# io-board-c-5.net
KiCad netlist of a schematic drawn in EAGLE
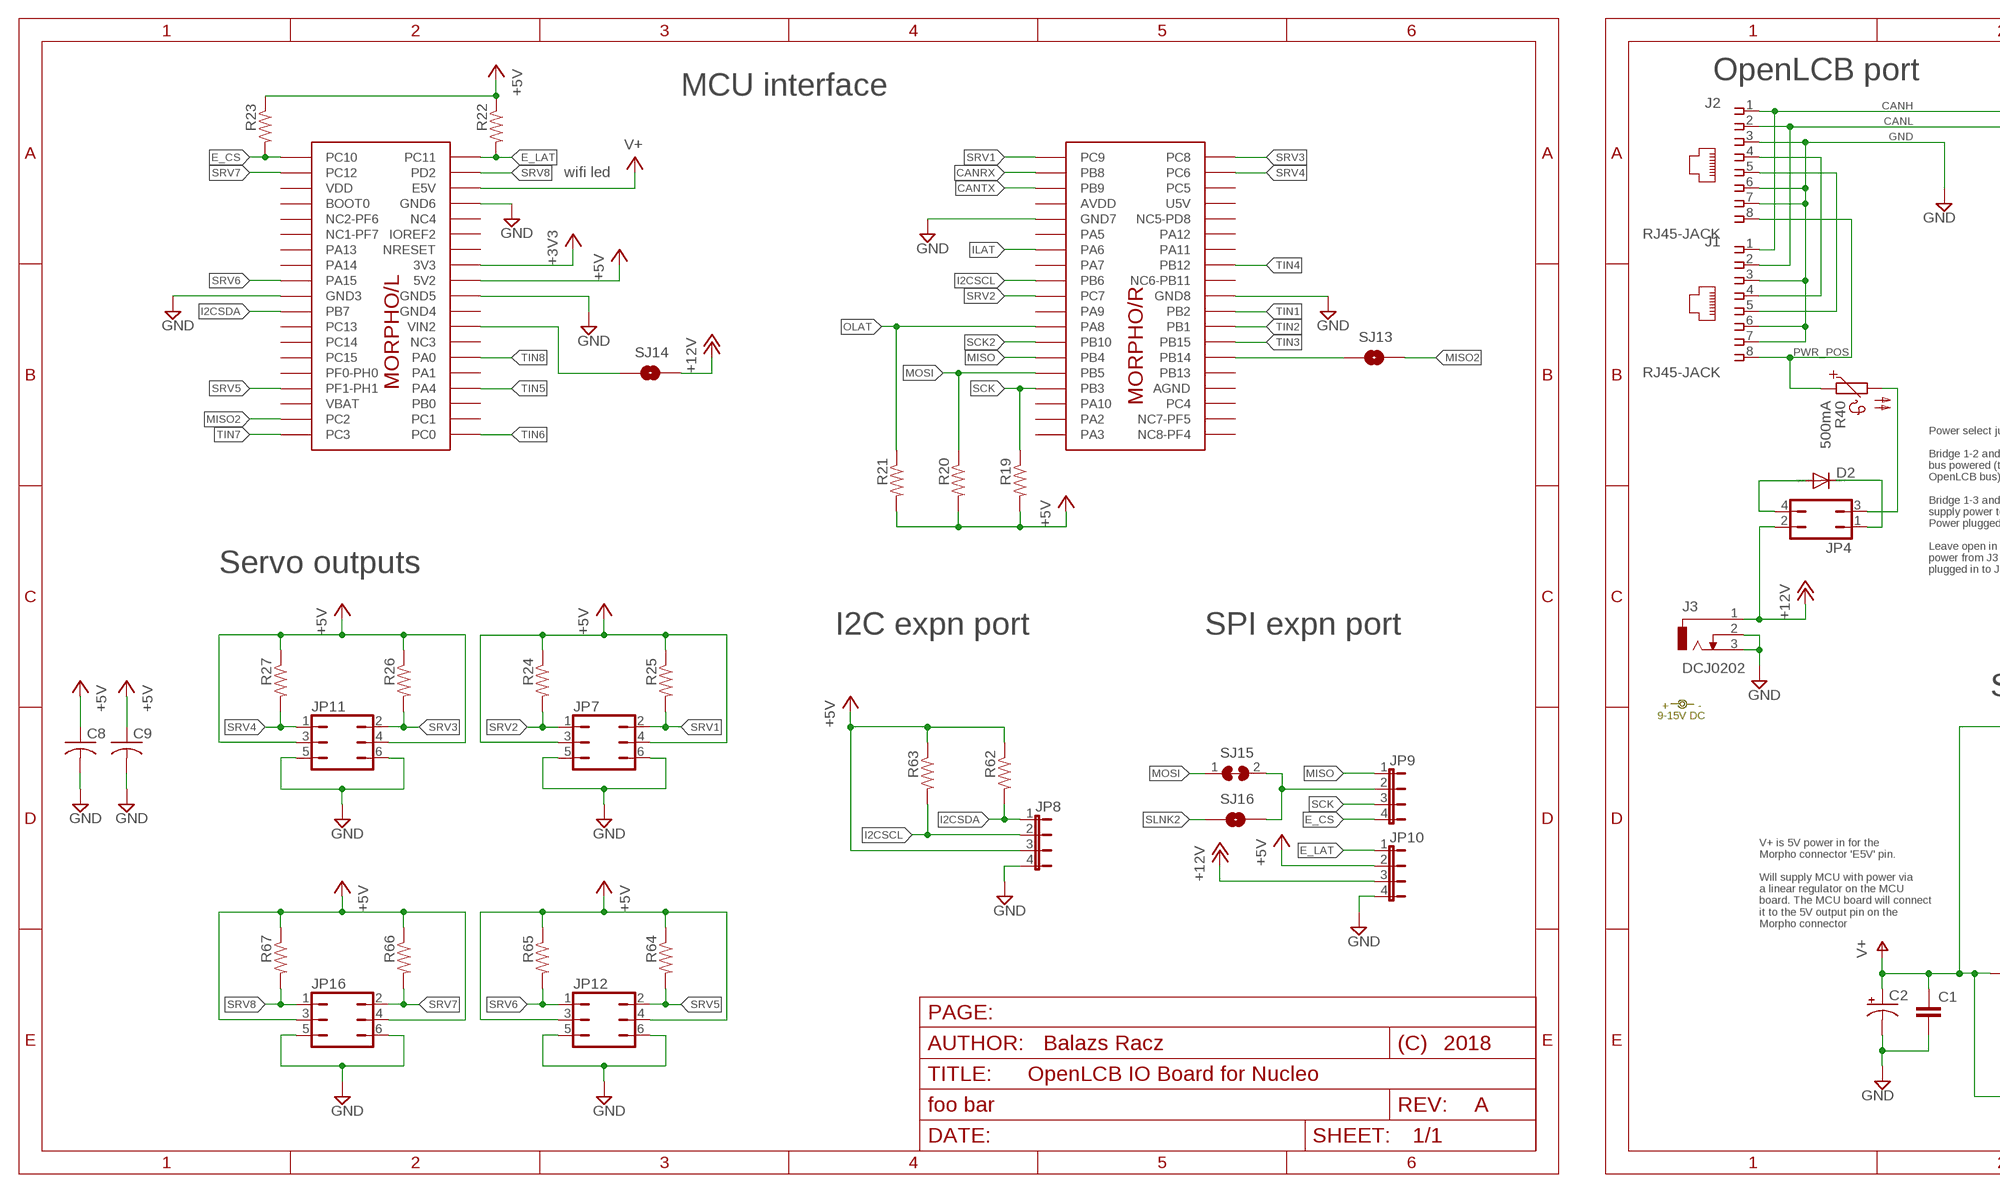
[diagram p0: schematic, sheet 1, part 1 of 3]
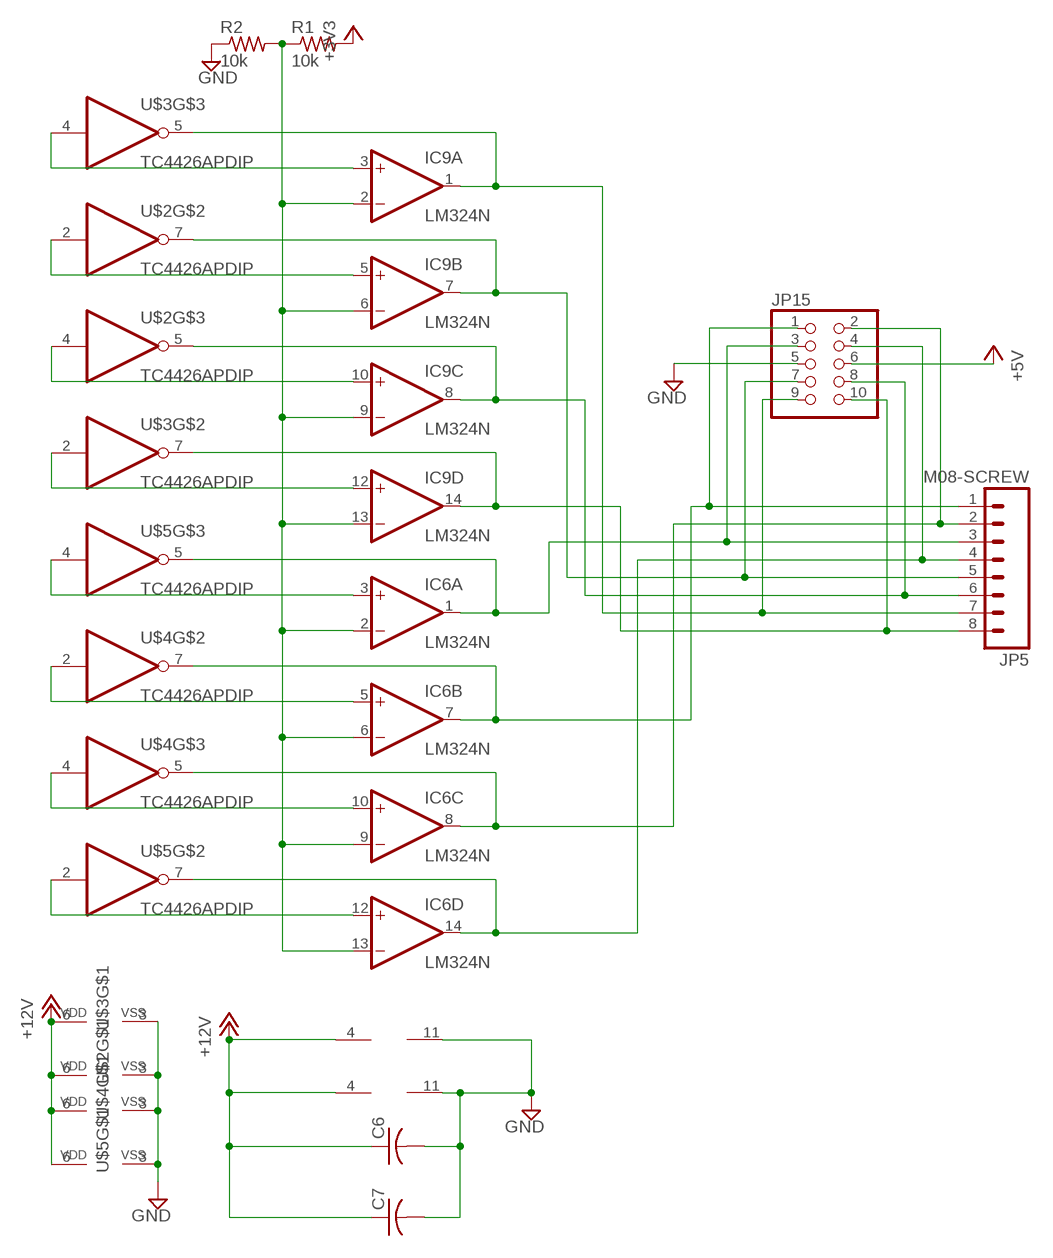
[diagram p1: schematic, sheet 1, part 2 of 3]
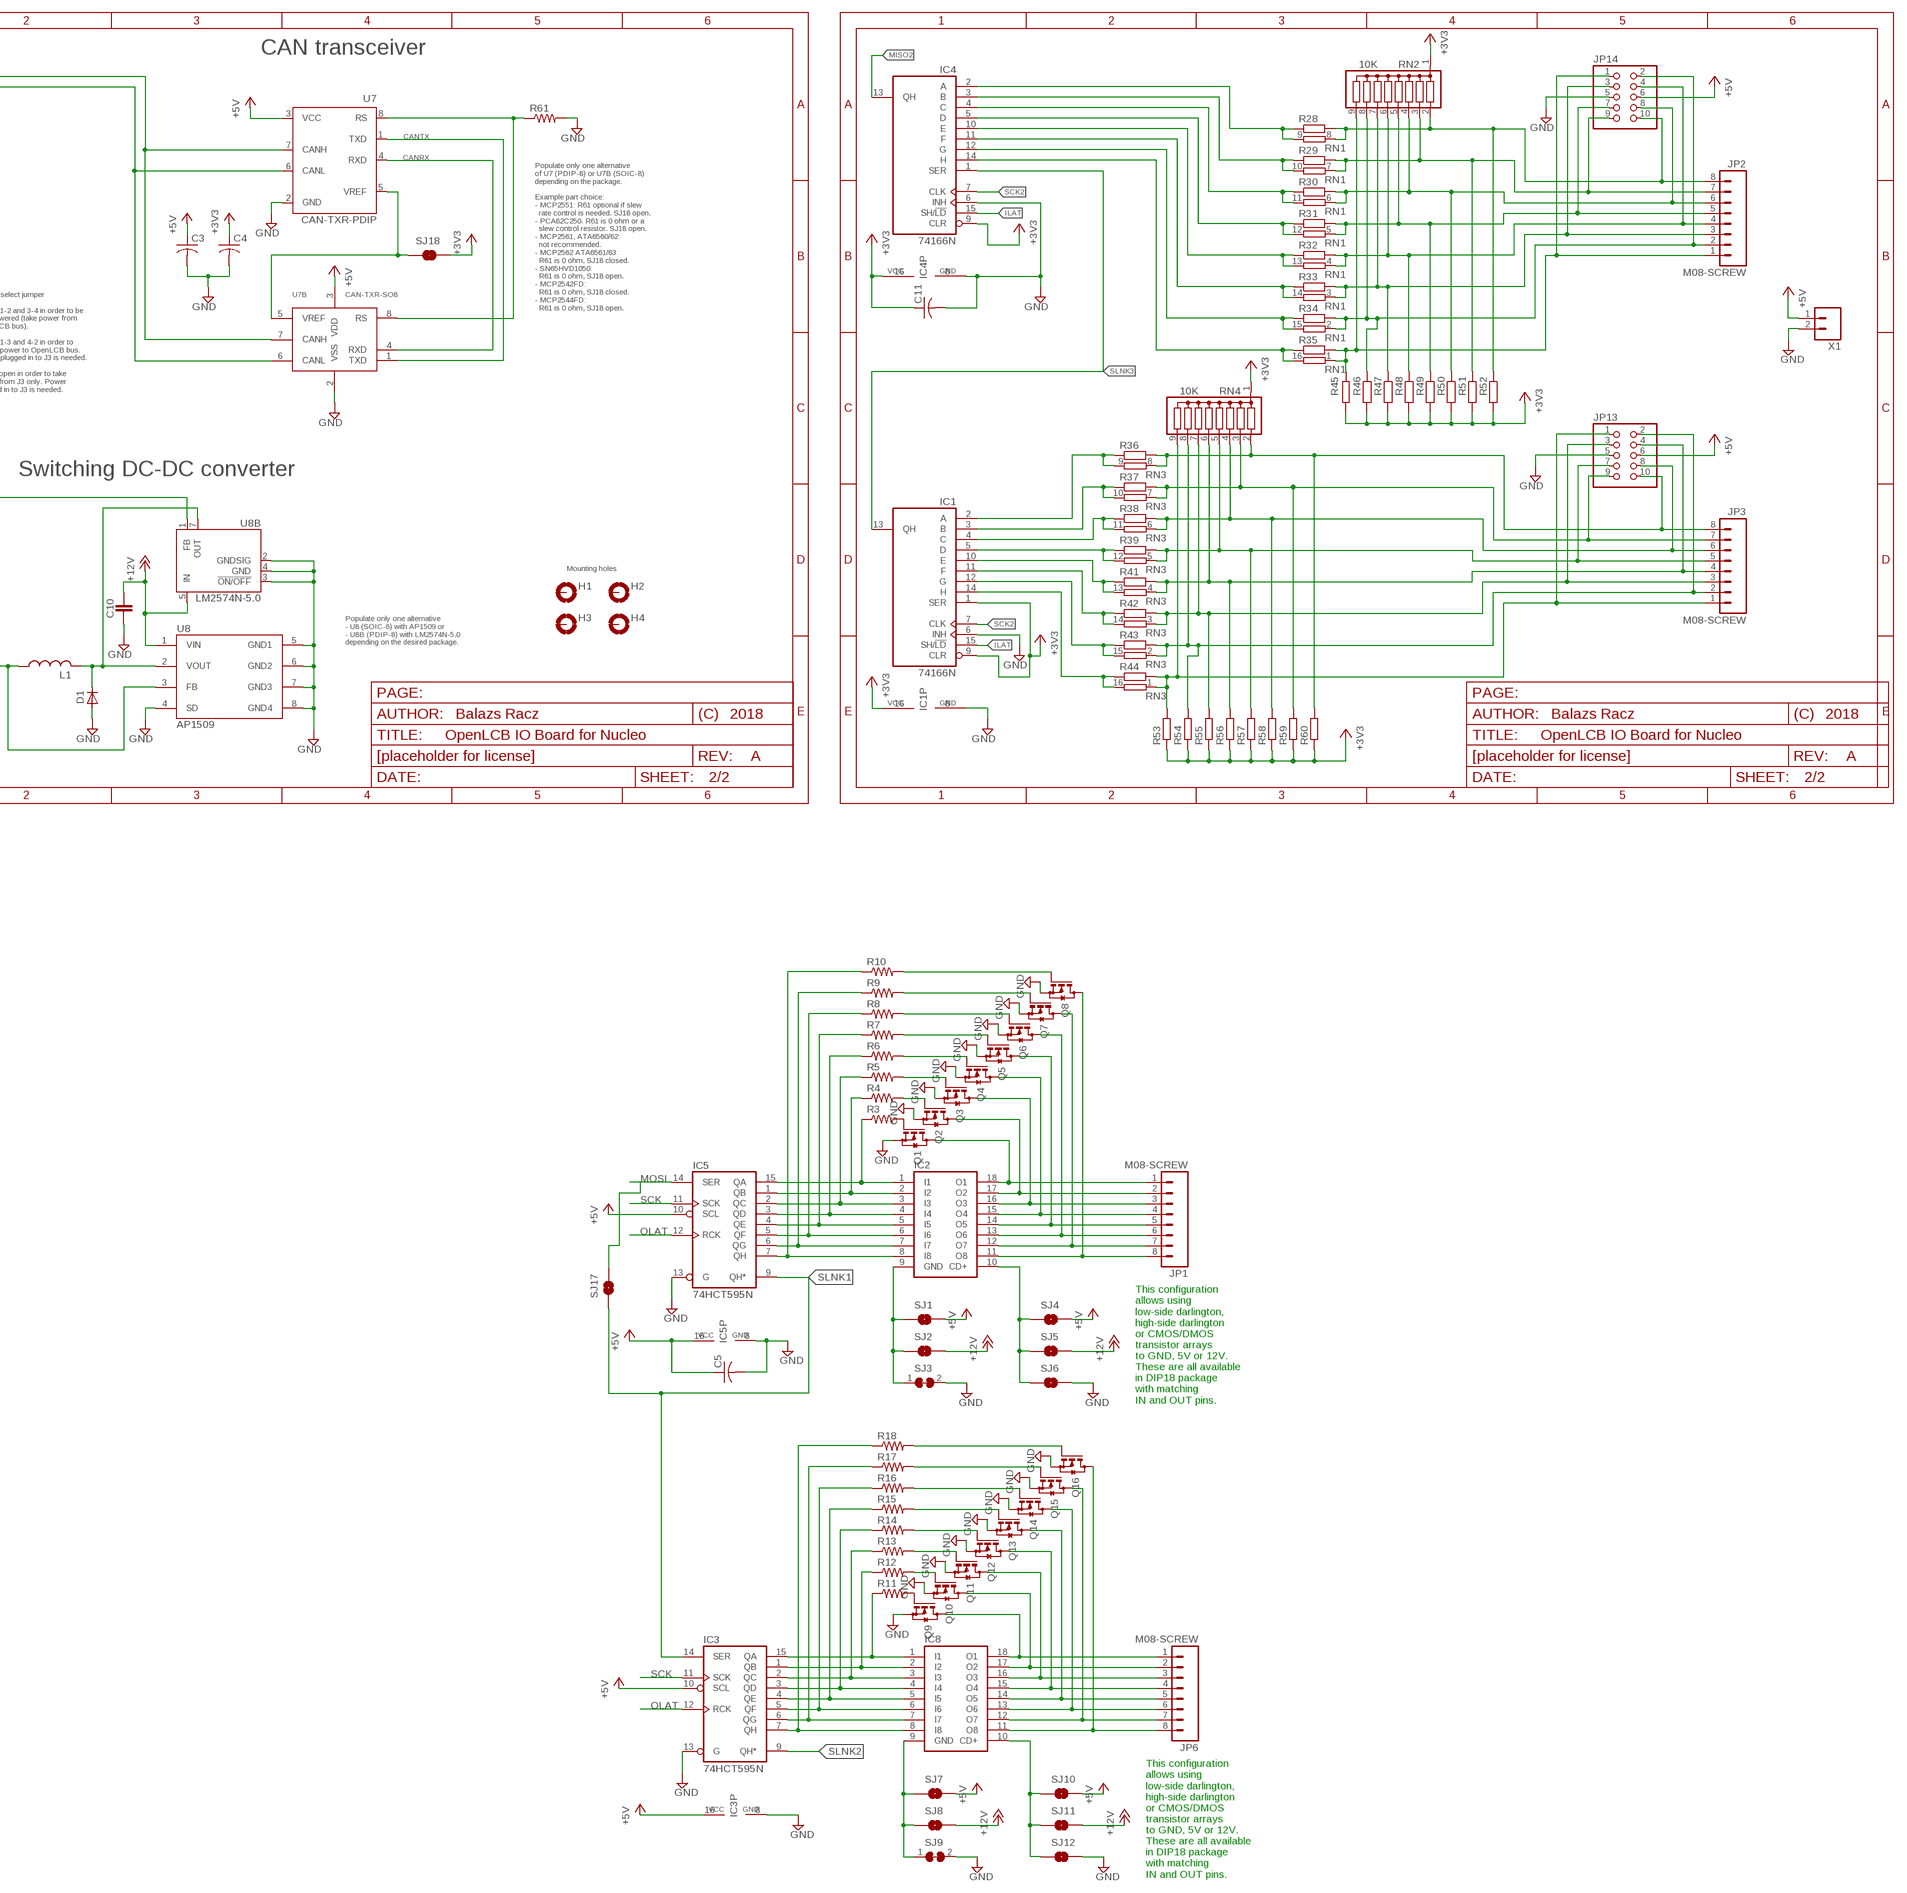
[diagram p2: schematic, sheet 1, part 3 of 3]

(export (version "E")
  (design (tool "Eeschema 10.0.6"))
  (components
    (comp (ref "+12V")
      (value "9-15V DC")
      (footprint "eagle-import:POWER_USAGE")
      (libsource (lib "eagle-import") (part "DOC-POWER_LABEL"))
    )
    (comp (ref "C1")
      (value "C-EUC1206")
      (footprint "eagle-import:C1206")
      (libsource (lib "eagle-import") (part "C-EUC1206"))
    )
    (comp (ref "C2")
      (value "CPOL-USE2.5-5")
      (footprint "eagle-import:E2,5-5")
      (libsource (lib "eagle-import") (part "CPOL-USE2.5-5"))
    )
    (comp (ref "C3")
      (value "C-USC0805")
      (footprint "eagle-import:C0805")
      (libsource (lib "eagle-import") (part "C-USC0805"))
    )
    (comp (ref "C4")
      (value "C-USC0805")
      (footprint "eagle-import:C0805")
      (libsource (lib "eagle-import") (part "C-USC0805"))
    )
    (comp (ref "C5")
      (value "C-USC0805")
      (footprint "eagle-import:C0805")
      (libsource (lib "eagle-import") (part "C-USC0805"))
    )
    (comp (ref "C6")
      (value "C-USC1206")
      (footprint "eagle-import:C1206")
      (libsource (lib "eagle-import") (part "C-USC1206"))
    )
    (comp (ref "C7")
      (value "C-USC1206")
      (footprint "eagle-import:C1206")
      (libsource (lib "eagle-import") (part "C-USC1206"))
    )
    (comp (ref "C8")
      (value "C-USC1206")
      (footprint "eagle-import:C1206")
      (libsource (lib "eagle-import") (part "C-USC1206"))
    )
    (comp (ref "C9")
      (value "C-USC1206")
      (footprint "eagle-import:C1206")
      (libsource (lib "eagle-import") (part "C-USC1206"))
    )
    (comp (ref "C10")
      (value "C-EUC1206")
      (footprint "eagle-import:C1206")
      (libsource (lib "eagle-import") (part "C-EUC1206"))
    )
    (comp (ref "C11")
      (value "C-USC0805")
      (footprint "eagle-import:C0805")
      (libsource (lib "eagle-import") (part "C-USC0805"))
    )
    (comp (ref "D1")
      (value "DIODE-DO41-7.6")
      (footprint "eagle-import:DO41-7.6")
      (libsource (lib "eagle-import") (part "DIODE-DO41-7.6"))
    )
    (comp (ref "D2")
      (value "DIODE-DO41-7.6")
      (footprint "eagle-import:DO41-7.6")
      (libsource (lib "eagle-import") (part "DIODE-DO41-7.6"))
    )
    (comp (ref "H1")
      (value "MOUNT-PAD-ROUND3.3")
      (footprint "eagle-import:3,3-PAD")
      (libsource (lib "eagle-import") (part "MOUNT-PAD-ROUND3.3"))
    )
    (comp (ref "H2")
      (value "MOUNT-PAD-ROUND3.3")
      (footprint "eagle-import:3,3-PAD")
      (libsource (lib "eagle-import") (part "MOUNT-PAD-ROUND3.3"))
    )
    (comp (ref "H3")
      (value "MOUNT-PAD-ROUND3.3")
      (footprint "eagle-import:3,3-PAD")
      (libsource (lib "eagle-import") (part "MOUNT-PAD-ROUND3.3"))
    )
    (comp (ref "H4")
      (value "MOUNT-PAD-ROUND3.3")
      (footprint "eagle-import:3,3-PAD")
      (libsource (lib "eagle-import") (part "MOUNT-PAD-ROUND3.3"))
    )
    (comp (ref "IC1")
      (value "74166N")
      (footprint "eagle-import:DIL16")
      (libsource (lib "eagle-import") (part "74166N"))
    )
    (comp (ref "IC2")
      (value "ULN2803A")
      (footprint "eagle-import:DIL18-THIN")
      (libsource (lib "eagle-import") (part "ULN2803A"))
    )
    (comp (ref "IC3")
      (value "74HCT595N")
      (footprint "eagle-import:DIL16")
      (libsource (lib "eagle-import") (part "74595NHCT"))
    )
    (comp (ref "IC4")
      (value "74166N")
      (footprint "eagle-import:DIL16")
      (libsource (lib "eagle-import") (part "74166N"))
    )
    (comp (ref "IC5")
      (value "74HCT595N")
      (footprint "eagle-import:DIL16")
      (libsource (lib "eagle-import") (part "74595NHCT"))
    )
    (comp (ref "IC6")
      (value "LM324N")
      (footprint "eagle-import:DIL14")
      (libsource (lib "eagle-import") (part "LM324N"))
    )
    (comp (ref "IC8")
      (value "ULN2803A")
      (footprint "eagle-import:DIL18-THIN")
      (libsource (lib "eagle-import") (part "ULN2803A"))
    )
    (comp (ref "IC9")
      (value "LM324N")
      (footprint "eagle-import:DIL14")
      (libsource (lib "eagle-import") (part "LM324N"))
    )
    (comp (ref "J1")
      (value "RJ45-JACK")
      (footprint "eagle-import:RJ45-PULSE-E5J88")
      (libsource (lib "eagle-import") (part "RJ45-JACKRJ45-PULSE-E5J00"))
    )
    (comp (ref "J2")
      (value "RJ45-JACK")
      (footprint "eagle-import:RJ45-PULSE-E5J88")
      (libsource (lib "eagle-import") (part "RJ45-JACKRJ45-PULSE-E5J00"))
    )
    (comp (ref "J3")
      (value "DCJ0202")
      (footprint "eagle-import:DCJ0202")
      (libsource (lib "eagle-import") (part "DCJ0202"))
    )
    (comp (ref "JP1")
      (value "M08-SCREW")
      (footprint "eagle-import:1X08_TERMINAL")
      (libsource (lib "eagle-import") (part "M08-SCREW"))
    )
    (comp (ref "JP2")
      (value "M08-SCREW")
      (footprint "eagle-import:1X08_TERMINAL")
      (libsource (lib "eagle-import") (part "M08-SCREW"))
    )
    (comp (ref "JP3")
      (value "M08-SCREW")
      (footprint "eagle-import:1X08_TERMINAL")
      (libsource (lib "eagle-import") (part "M08-SCREW"))
    )
    (comp (ref "JP4")
      (value "JP2Q")
      (footprint "eagle-import:JP2Q")
      (libsource (lib "eagle-import") (part "JP2Q"))
    )
    (comp (ref "JP5")
      (value "M08-SCREW")
      (footprint "eagle-import:1X08_TERMINAL")
      (libsource (lib "eagle-import") (part "M08-SCREW"))
    )
    (comp (ref "JP6")
      (value "M08-SCREW")
      (footprint "eagle-import:1X08_TERMINAL")
      (libsource (lib "eagle-import") (part "M08-SCREW"))
    )
    (comp (ref "JP7")
      (value "JP3Q")
      (footprint "eagle-import:JP3Q")
      (libsource (lib "eagle-import") (part "JP3Q"))
    )
    (comp (ref "JP8")
      (value "JP4-FLAT")
      (footprint "eagle-import:JP4F")
      (libsource (lib "eagle-import") (part "JP4-FLAT"))
    )
    (comp (ref "JP9")
      (value "JP4-FLAT")
      (footprint "eagle-import:JP4F")
      (libsource (lib "eagle-import") (part "JP4-FLAT"))
    )
    (comp (ref "JP10")
      (value "JP4-FLAT")
      (footprint "eagle-import:JP4F")
      (libsource (lib "eagle-import") (part "JP4-FLAT"))
    )
    (comp (ref "JP11")
      (value "JP3Q")
      (footprint "eagle-import:JP3Q")
      (libsource (lib "eagle-import") (part "JP3Q"))
    )
    (comp (ref "JP12")
      (value "JP3Q")
      (footprint "eagle-import:JP3Q")
      (libsource (lib "eagle-import") (part "JP3Q"))
    )
    (comp (ref "JP13")
      (value "PINHD-2X5CN")
      (footprint "eagle-import:CON10M")
      (libsource (lib "eagle-import") (part "PINHD-2X5CN"))
    )
    (comp (ref "JP14")
      (value "PINHD-2X5CN")
      (footprint "eagle-import:CON10M")
      (libsource (lib "eagle-import") (part "PINHD-2X5CN"))
    )
    (comp (ref "JP15")
      (value "PINHD-2X5CN")
      (footprint "eagle-import:CON10M")
      (libsource (lib "eagle-import") (part "PINHD-2X5CN"))
    )
    (comp (ref "JP16")
      (value "JP3Q")
      (footprint "eagle-import:JP3Q")
      (libsource (lib "eagle-import") (part "JP3Q"))
    )
    (comp (ref "L1")
      (value "L-US")
      (footprint "eagle-import:L5-8,5")
      (libsource (lib "eagle-import") (part "L-US"))
    )
    (comp (ref "Q1")
      (value "BSS123")
      (footprint "eagle-import:SOT23")
      (libsource (lib "eagle-import") (part "BSS123"))
    )
    (comp (ref "Q2")
      (value "BSS123")
      (footprint "eagle-import:SOT23")
      (libsource (lib "eagle-import") (part "BSS123"))
    )
    (comp (ref "Q3")
      (value "BSS123")
      (footprint "eagle-import:SOT23")
      (libsource (lib "eagle-import") (part "BSS123"))
    )
    (comp (ref "Q4")
      (value "BSS123")
      (footprint "eagle-import:SOT23")
      (libsource (lib "eagle-import") (part "BSS123"))
    )
    (comp (ref "Q5")
      (value "BSS123")
      (footprint "eagle-import:SOT23")
      (libsource (lib "eagle-import") (part "BSS123"))
    )
    (comp (ref "Q6")
      (value "BSS123")
      (footprint "eagle-import:SOT23")
      (libsource (lib "eagle-import") (part "BSS123"))
    )
    (comp (ref "Q7")
      (value "BSS123")
      (footprint "eagle-import:SOT23")
      (libsource (lib "eagle-import") (part "BSS123"))
    )
    (comp (ref "Q8")
      (value "BSS123")
      (footprint "eagle-import:SOT23")
      (libsource (lib "eagle-import") (part "BSS123"))
    )
    (comp (ref "Q9")
      (value "BSS123")
      (footprint "eagle-import:SOT23")
      (libsource (lib "eagle-import") (part "BSS123"))
    )
    (comp (ref "Q10")
      (value "BSS123")
      (footprint "eagle-import:SOT23")
      (libsource (lib "eagle-import") (part "BSS123"))
    )
    (comp (ref "Q11")
      (value "BSS123")
      (footprint "eagle-import:SOT23")
      (libsource (lib "eagle-import") (part "BSS123"))
    )
    (comp (ref "Q12")
      (value "BSS123")
      (footprint "eagle-import:SOT23")
      (libsource (lib "eagle-import") (part "BSS123"))
    )
    (comp (ref "Q13")
      (value "BSS123")
      (footprint "eagle-import:SOT23")
      (libsource (lib "eagle-import") (part "BSS123"))
    )
    (comp (ref "Q14")
      (value "BSS123")
      (footprint "eagle-import:SOT23")
      (libsource (lib "eagle-import") (part "BSS123"))
    )
    (comp (ref "Q15")
      (value "BSS123")
      (footprint "eagle-import:SOT23")
      (libsource (lib "eagle-import") (part "BSS123"))
    )
    (comp (ref "Q16")
      (value "BSS123")
      (footprint "eagle-import:SOT23")
      (libsource (lib "eagle-import") (part "BSS123"))
    )
    (comp (ref "R1")
      (value "10k")
      (footprint "eagle-import:R0805")
      (libsource (lib "eagle-import") (part "R-US_R0805"))
    )
    (comp (ref "R2")
      (value "10k")
      (footprint "eagle-import:R0805")
      (libsource (lib "eagle-import") (part "R-US_R0805"))
    )
    (comp (ref "R3")
      (value "R-US_R0603")
      (footprint "eagle-import:R0603")
      (libsource (lib "eagle-import") (part "R-US_R0603"))
    )
    (comp (ref "R4")
      (value "R-US_R0603")
      (footprint "eagle-import:R0603")
      (libsource (lib "eagle-import") (part "R-US_R0603"))
    )
    (comp (ref "R5")
      (value "R-US_R0603")
      (footprint "eagle-import:R0603")
      (libsource (lib "eagle-import") (part "R-US_R0603"))
    )
    (comp (ref "R6")
      (value "R-US_R0603")
      (footprint "eagle-import:R0603")
      (libsource (lib "eagle-import") (part "R-US_R0603"))
    )
    (comp (ref "R7")
      (value "R-US_R0603")
      (footprint "eagle-import:R0603")
      (libsource (lib "eagle-import") (part "R-US_R0603"))
    )
    (comp (ref "R8")
      (value "R-US_R0603")
      (footprint "eagle-import:R0603")
      (libsource (lib "eagle-import") (part "R-US_R0603"))
    )
    (comp (ref "R9")
      (value "R-US_R0603")
      (footprint "eagle-import:R0603")
      (libsource (lib "eagle-import") (part "R-US_R0603"))
    )
    (comp (ref "R10")
      (value "R-US_R0603")
      (footprint "eagle-import:R0603")
      (libsource (lib "eagle-import") (part "R-US_R0603"))
    )
    (comp (ref "R11")
      (value "R-US_R0603")
      (footprint "eagle-import:R0603")
      (libsource (lib "eagle-import") (part "R-US_R0603"))
    )
    (comp (ref "R12")
      (value "R-US_R0603")
      (footprint "eagle-import:R0603")
      (libsource (lib "eagle-import") (part "R-US_R0603"))
    )
    (comp (ref "R13")
      (value "R-US_R0603")
      (footprint "eagle-import:R0603")
      (libsource (lib "eagle-import") (part "R-US_R0603"))
    )
    (comp (ref "R14")
      (value "R-US_R0603")
      (footprint "eagle-import:R0603")
      (libsource (lib "eagle-import") (part "R-US_R0603"))
    )
    (comp (ref "R15")
      (value "R-US_R0603")
      (footprint "eagle-import:R0603")
      (libsource (lib "eagle-import") (part "R-US_R0603"))
    )
    (comp (ref "R16")
      (value "R-US_R0603")
      (footprint "eagle-import:R0603")
      (libsource (lib "eagle-import") (part "R-US_R0603"))
    )
    (comp (ref "R17")
      (value "R-US_R0603")
      (footprint "eagle-import:R0603")
      (libsource (lib "eagle-import") (part "R-US_R0603"))
    )
    (comp (ref "R18")
      (value "R-US_R0603")
      (footprint "eagle-import:R0603")
      (libsource (lib "eagle-import") (part "R-US_R0603"))
    )
    (comp (ref "R19")
      (value "R-US_R0805")
      (footprint "eagle-import:R0805")
      (libsource (lib "eagle-import") (part "rcl_334_R-US_R0805"))
    )
    (comp (ref "R20")
      (value "R-US_R0805")
      (footprint "eagle-import:R0805")
      (libsource (lib "eagle-import") (part "rcl_334_R-US_R0805"))
    )
    (comp (ref "R21")
      (value "R-US_R0805")
      (footprint "eagle-import:R0805")
      (libsource (lib "eagle-import") (part "rcl_334_R-US_R0805"))
    )
    (comp (ref "R22")
      (value "R-US_R0805")
      (footprint "eagle-import:R0805")
      (libsource (lib "eagle-import") (part "rcl_334_R-US_R0805"))
    )
    (comp (ref "R23")
      (value "R-US_R0805")
      (footprint "eagle-import:R0805")
      (libsource (lib "eagle-import") (part "rcl_334_R-US_R0805"))
    )
    (comp (ref "R24")
      (value "R-US_R0805")
      (footprint "eagle-import:R0805")
      (libsource (lib "eagle-import") (part "rcl_334_R-US_R0805"))
    )
    (comp (ref "R25")
      (value "R-US_R0805")
      (footprint "eagle-import:R0805")
      (libsource (lib "eagle-import") (part "rcl_334_R-US_R0805"))
    )
    (comp (ref "R26")
      (value "R-US_R0805")
      (footprint "eagle-import:R0805")
      (libsource (lib "eagle-import") (part "rcl_334_R-US_R0805"))
    )
    (comp (ref "R27")
      (value "R-US_R0805")
      (footprint "eagle-import:R0805")
      (libsource (lib "eagle-import") (part "rcl_334_R-US_R0805"))
    )
    (comp (ref "R28")
      (value "R-EU_R0603")
      (footprint "eagle-import:R0603")
      (libsource (lib "eagle-import") (part "R-EU_R0603"))
    )
    (comp (ref "R29")
      (value "R-EU_R0603")
      (footprint "eagle-import:R0603")
      (libsource (lib "eagle-import") (part "R-EU_R0603"))
    )
    (comp (ref "R30")
      (value "R-EU_R0603")
      (footprint "eagle-import:R0603")
      (libsource (lib "eagle-import") (part "R-EU_R0603"))
    )
    (comp (ref "R31")
      (value "R-EU_R0603")
      (footprint "eagle-import:R0603")
      (libsource (lib "eagle-import") (part "R-EU_R0603"))
    )
    (comp (ref "R32")
      (value "R-EU_R0603")
      (footprint "eagle-import:R0603")
      (libsource (lib "eagle-import") (part "R-EU_R0603"))
    )
    (comp (ref "R33")
      (value "R-EU_R0603")
      (footprint "eagle-import:R0603")
      (libsource (lib "eagle-import") (part "R-EU_R0603"))
    )
    (comp (ref "R34")
      (value "R-EU_R0603")
      (footprint "eagle-import:R0603")
      (libsource (lib "eagle-import") (part "R-EU_R0603"))
    )
    (comp (ref "R35")
      (value "R-EU_R0603")
      (footprint "eagle-import:R0603")
      (libsource (lib "eagle-import") (part "R-EU_R0603"))
    )
    (comp (ref "R36")
      (value "R-EU_R0603")
      (footprint "eagle-import:R0603")
      (libsource (lib "eagle-import") (part "R-EU_R0603"))
    )
    (comp (ref "R37")
      (value "R-EU_R0603")
      (footprint "eagle-import:R0603")
      (libsource (lib "eagle-import") (part "R-EU_R0603"))
    )
    (comp (ref "R38")
      (value "R-EU_R0603")
      (footprint "eagle-import:R0603")
      (libsource (lib "eagle-import") (part "R-EU_R0603"))
    )
    (comp (ref "R39")
      (value "R-EU_R0603")
      (footprint "eagle-import:R0603")
      (libsource (lib "eagle-import") (part "R-EU_R0603"))
    )
    (comp (ref "R40")
      (value "500mA")
      (footprint "eagle-import:PTC1812")
      (libsource (lib "eagle-import") (part "PTC_1812"))
    )
    (comp (ref "R41")
      (value "R-EU_R0603")
      (footprint "eagle-import:R0603")
      (libsource (lib "eagle-import") (part "R-EU_R0603"))
    )
    (comp (ref "R42")
      (value "R-EU_R0603")
      (footprint "eagle-import:R0603")
      (libsource (lib "eagle-import") (part "R-EU_R0603"))
    )
    (comp (ref "R43")
      (value "R-EU_R0603")
      (footprint "eagle-import:R0603")
      (libsource (lib "eagle-import") (part "R-EU_R0603"))
    )
    (comp (ref "R44")
      (value "R-EU_R0603")
      (footprint "eagle-import:R0603")
      (libsource (lib "eagle-import") (part "R-EU_R0603"))
    )
    (comp (ref "R45")
      (value "R-EU_R0603")
      (footprint "eagle-import:R0603")
      (libsource (lib "eagle-import") (part "R-EU_R0603"))
    )
    (comp (ref "R46")
      (value "R-EU_R0603")
      (footprint "eagle-import:R0603")
      (libsource (lib "eagle-import") (part "R-EU_R0603"))
    )
    (comp (ref "R47")
      (value "R-EU_R0603")
      (footprint "eagle-import:R0603")
      (libsource (lib "eagle-import") (part "R-EU_R0603"))
    )
    (comp (ref "R48")
      (value "R-EU_R0603")
      (footprint "eagle-import:R0603")
      (libsource (lib "eagle-import") (part "R-EU_R0603"))
    )
    (comp (ref "R49")
      (value "R-EU_R0603")
      (footprint "eagle-import:R0603")
      (libsource (lib "eagle-import") (part "R-EU_R0603"))
    )
    (comp (ref "R50")
      (value "R-EU_R0603")
      (footprint "eagle-import:R0603")
      (libsource (lib "eagle-import") (part "R-EU_R0603"))
    )
    (comp (ref "R51")
      (value "R-EU_R0603")
      (footprint "eagle-import:R0603")
      (libsource (lib "eagle-import") (part "R-EU_R0603"))
    )
    (comp (ref "R52")
      (value "R-EU_R0603")
      (footprint "eagle-import:R0603")
      (libsource (lib "eagle-import") (part "R-EU_R0603"))
    )
    (comp (ref "R53")
      (value "R-EU_R0603")
      (footprint "eagle-import:R0603")
      (libsource (lib "eagle-import") (part "R-EU_R0603"))
    )
    (comp (ref "R54")
      (value "R-EU_R0603")
      (footprint "eagle-import:R0603")
      (libsource (lib "eagle-import") (part "R-EU_R0603"))
    )
    (comp (ref "R55")
      (value "R-EU_R0603")
      (footprint "eagle-import:R0603")
      (libsource (lib "eagle-import") (part "R-EU_R0603"))
    )
    (comp (ref "R56")
      (value "R-EU_R0603")
      (footprint "eagle-import:R0603")
      (libsource (lib "eagle-import") (part "R-EU_R0603"))
    )
    (comp (ref "R57")
      (value "R-EU_R0603")
      (footprint "eagle-import:R0603")
      (libsource (lib "eagle-import") (part "R-EU_R0603"))
    )
    (comp (ref "R58")
      (value "R-EU_R0603")
      (footprint "eagle-import:R0603")
      (libsource (lib "eagle-import") (part "R-EU_R0603"))
    )
    (comp (ref "R59")
      (value "R-EU_R0603")
      (footprint "eagle-import:R0603")
      (libsource (lib "eagle-import") (part "R-EU_R0603"))
    )
    (comp (ref "R60")
      (value "R-EU_R0603")
      (footprint "eagle-import:R0603")
      (libsource (lib "eagle-import") (part "R-EU_R0603"))
    )
    (comp (ref "R61")
      (value "R-US_R0805")
      (footprint "eagle-import:R0805")
      (libsource (lib "eagle-import") (part "rcl_334_R-US_R0805"))
    )
    (comp (ref "R62")
      (value "R-US_R0805")
      (footprint "eagle-import:R0805")
      (libsource (lib "eagle-import") (part "rcl_334_R-US_R0805"))
    )
    (comp (ref "R63")
      (value "R-US_R0805")
      (footprint "eagle-import:R0805")
      (libsource (lib "eagle-import") (part "rcl_334_R-US_R0805"))
    )
    (comp (ref "R64")
      (value "R-US_R0805")
      (footprint "eagle-import:R0805")
      (libsource (lib "eagle-import") (part "rcl_334_R-US_R0805"))
    )
    (comp (ref "R65")
      (value "R-US_R0805")
      (footprint "eagle-import:R0805")
      (libsource (lib "eagle-import") (part "rcl_334_R-US_R0805"))
    )
    (comp (ref "R66")
      (value "R-US_R0805")
      (footprint "eagle-import:R0805")
      (libsource (lib "eagle-import") (part "rcl_334_R-US_R0805"))
    )
    (comp (ref "R67")
      (value "R-US_R0805")
      (footprint "eagle-import:R0805")
      (libsource (lib "eagle-import") (part "rcl_334_R-US_R0805"))
    )
    (comp (ref "RN1")
      (value "8R-P")
      (footprint "eagle-import:DIL16")
      (libsource (lib "eagle-import") (part "8R-P"))
    )
    (comp (ref "RN2")
      (value "10K")
      (footprint "eagle-import:SIL9")
      (libsource (lib "eagle-import") (part "G08R"))
    )
    (comp (ref "RN3")
      (value "8R-P")
      (footprint "eagle-import:DIL16")
      (libsource (lib "eagle-import") (part "8R-P"))
    )
    (comp (ref "RN4")
      (value "10K")
      (footprint "eagle-import:SIL9")
      (libsource (lib "eagle-import") (part "G08R"))
    )
    (comp (ref "SJ1")
      (value "SJRND2")
      (footprint "eagle-import:SJ_RND2")
      (libsource (lib "eagle-import") (part "SJRND2"))
    )
    (comp (ref "SJ2")
      (value "SJRND2")
      (footprint "eagle-import:SJ_RND2")
      (libsource (lib "eagle-import") (part "SJRND2"))
    )
    (comp (ref "SJ3")
      (value "SJ-C")
      (footprint "eagle-import:SJW-C")
      (libsource (lib "eagle-import") (part "SJ-C"))
    )
    (comp (ref "SJ4")
      (value "SJRND2")
      (footprint "eagle-import:SJ_RND2")
      (libsource (lib "eagle-import") (part "SJRND2"))
    )
    (comp (ref "SJ5")
      (value "SJRND2")
      (footprint "eagle-import:SJ_RND2")
      (libsource (lib "eagle-import") (part "SJRND2"))
    )
    (comp (ref "SJ6")
      (value "SJRND2")
      (footprint "eagle-import:SJ_RND2")
      (libsource (lib "eagle-import") (part "SJRND2"))
    )
    (comp (ref "SJ7")
      (value "SJRND2")
      (footprint "eagle-import:SJ_RND2")
      (libsource (lib "eagle-import") (part "SJRND2"))
    )
    (comp (ref "SJ8")
      (value "SJRND2")
      (footprint "eagle-import:SJ_RND2")
      (libsource (lib "eagle-import") (part "SJRND2"))
    )
    (comp (ref "SJ9")
      (value "SJ-C")
      (footprint "eagle-import:SJW-C")
      (libsource (lib "eagle-import") (part "SJ-C"))
    )
    (comp (ref "SJ10")
      (value "SJRND2")
      (footprint "eagle-import:SJ_RND2")
      (libsource (lib "eagle-import") (part "SJRND2"))
    )
    (comp (ref "SJ11")
      (value "SJRND2")
      (footprint "eagle-import:SJ_RND2")
      (libsource (lib "eagle-import") (part "SJRND2"))
    )
    (comp (ref "SJ12")
      (value "SJRND2")
      (footprint "eagle-import:SJ_RND2")
      (libsource (lib "eagle-import") (part "SJRND2"))
    )
    (comp (ref "SJ13")
      (value "SJRND2")
      (footprint "eagle-import:SJ_RND2")
      (libsource (lib "eagle-import") (part "SJRND2"))
    )
    (comp (ref "SJ14")
      (value "SJRND2")
      (footprint "eagle-import:SJ_RND2")
      (libsource (lib "eagle-import") (part "SJRND2"))
    )
    (comp (ref "SJ15")
      (value "SJ-C")
      (footprint "eagle-import:SJW-C")
      (libsource (lib "eagle-import") (part "SJ-C"))
    )
    (comp (ref "SJ16")
      (value "SJRND2")
      (footprint "eagle-import:SJ_RND2")
      (libsource (lib "eagle-import") (part "SJRND2"))
    )
    (comp (ref "SJ17")
      (value "SJRND2")
      (footprint "eagle-import:SJ_RND2")
      (libsource (lib "eagle-import") (part "SJRND2"))
    )
    (comp (ref "SJ18")
      (value "SJRND2")
      (footprint "eagle-import:SJ_RND2")
      (libsource (lib "eagle-import") (part "SJRND2"))
    )
    (comp (ref "U$1")
      (value "NUCLEO_64_GENERIC")
      (footprint "eagle-import:NUCLEO_BRD_BASE64")
      (libsource (lib "eagle-import") (part "NUCLEO_64_GENERIC"))
    )
    (comp (ref "U$2")
      (value "TC4426APDIP")
      (footprint "eagle-import:DIL08-LONG")
      (libsource (lib "eagle-import") (part "TC4426APDIP"))
    )
    (comp (ref "U$3")
      (value "TC4426APDIP")
      (footprint "eagle-import:DIL08-LONG")
      (libsource (lib "eagle-import") (part "TC4426APDIP"))
    )
    (comp (ref "U$4")
      (value "TC4426APDIP")
      (footprint "eagle-import:DIL08-LONG")
      (libsource (lib "eagle-import") (part "TC4426APDIP"))
    )
    (comp (ref "U$5")
      (value "TC4426APDIP")
      (footprint "eagle-import:DIL08-LONG")
      (libsource (lib "eagle-import") (part "TC4426APDIP"))
    )
    (comp (ref "U7")
      (value "CAN-TXR-PDIP")
      (footprint "eagle-import:DIL08")
      (libsource (lib "eagle-import") (part "PCA82C250"))
    )
    (comp (ref "U7B")
      (value "CAN-TXR-SO8")
      (footprint "eagle-import:SO-08")
      (libsource (lib "eagle-import") (part "MCP2551-SN"))
    )
    (comp (ref "U8")
      (value "AP1509")
      (footprint "eagle-import:SO-08")
      (libsource (lib "eagle-import") (part "AP1509"))
    )
    (comp (ref "U8B")
      (value "LM2574N-5.0")
      (footprint "eagle-import:DIL08")
      (libsource (lib "eagle-import") (part "LM2574?-N5.0"))
    )
    (comp (ref "X1")
      (value "CONNECTOR-M023.5MM-LOCK")
      (footprint "eagle-import:SCREWTERMINAL-3.5MM-2_LOCK")
      (libsource (lib "eagle-import") (part "CONNECTOR-M023.5MM-LOCK"))
    )
  )
  (nets
    (net (code "1") (name "+3V3") (class "Default")
      (node (ref "C11") (pin "1") (pinfunction "1_1") (pintype "passive"))
      (node (ref "C4") (pin "1") (pinfunction "1_1") (pintype "passive"))
      (node (ref "IC1") (pin "1") (pinfunction "SER_1") (pintype "input"))
      (node (ref "IC1") (pin "16") (pinfunction "VCC_16") (pintype "power_in"))
      (node (ref "IC1") (pin "9") (pinfunction "CLR_9") (pintype "input"))
      (node (ref "IC4") (pin "16") (pinfunction "VCC_16") (pintype "power_in"))
      (node (ref "IC4") (pin "9") (pinfunction "CLR_9") (pintype "input"))
      (node (ref "R1") (pin "2") (pinfunction "2_2") (pintype "passive"))
      (node (ref "R45") (pin "1") (pinfunction "1_1") (pintype "passive"))
      (node (ref "R46") (pin "2") (pinfunction "2_2") (pintype "passive"))
      (node (ref "R47") (pin "2") (pinfunction "2_2") (pintype "passive"))
      (node (ref "R48") (pin "2") (pinfunction "2_2") (pintype "passive"))
      (node (ref "R49") (pin "2") (pinfunction "2_2") (pintype "passive"))
      (node (ref "R50") (pin "2") (pinfunction "2_2") (pintype "passive"))
      (node (ref "R51") (pin "2") (pinfunction "2_2") (pintype "passive"))
      (node (ref "R52") (pin "2") (pinfunction "2_2") (pintype "passive"))
      (node (ref "R53") (pin "1") (pinfunction "1_1") (pintype "passive"))
      (node (ref "R54") (pin "1") (pinfunction "1_1") (pintype "passive"))
      (node (ref "R55") (pin "1") (pinfunction "1_1") (pintype "passive"))
      (node (ref "R56") (pin "1") (pinfunction "1_1") (pintype "passive"))
      (node (ref "R57") (pin "1") (pinfunction "1_1") (pintype "passive"))
      (node (ref "R58") (pin "1") (pinfunction "1_1") (pintype "passive"))
      (node (ref "R59") (pin "1") (pinfunction "1_1") (pintype "passive"))
      (node (ref "R60") (pin "1") (pinfunction "1_1") (pintype "passive"))
      (node (ref "RN2") (pin "1") (pinfunction "1_1") (pintype "passive"))
      (node (ref "RN4") (pin "1") (pinfunction "1_1") (pintype "passive"))
      (node (ref "SJ18") (pin "P$1") (pinfunction "1_P$1") (pintype "passive"))
      (node (ref "U$1") (pin "3V3") (pinfunction "3V3_3V3") (pintype "power_in"))
    )
    (net (code "2") (name "+5V") (class "Default")
      (node (ref "C3") (pin "1") (pinfunction "1_1") (pintype "passive"))
      (node (ref "C5") (pin "1") (pinfunction "1_1") (pintype "passive"))
      (node (ref "C8") (pin "1") (pinfunction "1_1") (pintype "passive"))
      (node (ref "C9") (pin "1") (pinfunction "1_1") (pintype "passive"))
      (node (ref "IC3") (pin "10") (pinfunction "SCL_10") (pintype "input"))
      (node (ref "IC3") (pin "16") (pinfunction "VCC_16") (pintype "power_in"))
      (node (ref "IC5") (pin "10") (pinfunction "SCL_10") (pintype "input"))
      (node (ref "IC5") (pin "16") (pinfunction "VCC_16") (pintype "power_in"))
      (node (ref "JP10") (pin "2") (pinfunction "2_2") (pintype "passive"))
      (node (ref "JP11") (pin "3") (pinfunction "3_3") (pintype "passive"))
      (node (ref "JP11") (pin "4") (pinfunction "4_4") (pintype "passive"))
      (node (ref "JP12") (pin "3") (pinfunction "3_3") (pintype "passive"))
      (node (ref "JP12") (pin "4") (pinfunction "4_4") (pintype "passive"))
      (node (ref "JP13") (pin "6") (pinfunction "6_6") (pintype "passive"))
      (node (ref "JP14") (pin "6") (pinfunction "6_6") (pintype "passive"))
      (node (ref "JP15") (pin "6") (pinfunction "6_6") (pintype "passive"))
      (node (ref "JP16") (pin "3") (pinfunction "3_3") (pintype "passive"))
      (node (ref "JP16") (pin "4") (pinfunction "4_4") (pintype "passive"))
      (node (ref "JP7") (pin "3") (pinfunction "3_3") (pintype "passive"))
      (node (ref "JP7") (pin "4") (pinfunction "4_4") (pintype "passive"))
      (node (ref "JP8") (pin "3") (pinfunction "3_3") (pintype "passive"))
      (node (ref "R19") (pin "2") (pinfunction "2_2") (pintype "passive"))
      (node (ref "R20") (pin "2") (pinfunction "2_2") (pintype "passive"))
      (node (ref "R21") (pin "2") (pinfunction "2_2") (pintype "passive"))
      (node (ref "R22") (pin "1") (pinfunction "1_1") (pintype "passive"))
      (node (ref "R23") (pin "1") (pinfunction "1_1") (pintype "passive"))
      (node (ref "R24") (pin "1") (pinfunction "1_1") (pintype "passive"))
      (node (ref "R25") (pin "1") (pinfunction "1_1") (pintype "passive"))
      (node (ref "R26") (pin "1") (pinfunction "1_1") (pintype "passive"))
      (node (ref "R27") (pin "1") (pinfunction "1_1") (pintype "passive"))
      (node (ref "R62") (pin "1") (pinfunction "1_1") (pintype "passive"))
      (node (ref "R63") (pin "1") (pinfunction "1_1") (pintype "passive"))
      (node (ref "R64") (pin "1") (pinfunction "1_1") (pintype "passive"))
      (node (ref "R65") (pin "1") (pinfunction "1_1") (pintype "passive"))
      (node (ref "R66") (pin "1") (pinfunction "1_1") (pintype "passive"))
      (node (ref "R67") (pin "1") (pinfunction "1_1") (pintype "passive"))
      (node (ref "SJ1") (pin "P$2") (pinfunction "2_P$2") (pintype "passive"))
      (node (ref "SJ10") (pin "P$2") (pinfunction "2_P$2") (pintype "passive"))
      (node (ref "SJ4") (pin "P$2") (pinfunction "2_P$2") (pintype "passive"))
      (node (ref "SJ7") (pin "P$2") (pinfunction "2_P$2") (pintype "passive"))
      (node (ref "U$1") (pin "5V2") (pinfunction "5V2_5V2") (pintype "power_in"))
      (node (ref "U7") (pin "3") (pinfunction "VCC_3") (pintype "power_in"))
      (node (ref "U7B") (pin "3") (pinfunction "VDD_3") (pintype "power_in"))
      (node (ref "X1") (pin "1") (pinfunction "1_1") (pintype "passive"))
    )
    (net (code "3") (name "+12V") (class "Default")
      (node (ref "C10") (pin "1") (pinfunction "1_1") (pintype "passive"))
      (node (ref "C6") (pin "1") (pinfunction "1_1") (pintype "passive"))
      (node (ref "C7") (pin "1") (pinfunction "1_1") (pintype "passive"))
      (node (ref "IC6") (pin "4") (pinfunction "V+_4") (pintype "power_in"))
      (node (ref "IC9") (pin "4") (pinfunction "V+_4") (pintype "power_in"))
      (node (ref "J3") (pin "1") (pinfunction "1_1") (pintype "passive"))
      (node (ref "JP10") (pin "3") (pinfunction "3_3") (pintype "passive"))
      (node (ref "JP4") (pin "2") (pinfunction "2_2") (pintype "passive"))
      (node (ref "SJ11") (pin "P$2") (pinfunction "2_P$2") (pintype "passive"))
      (node (ref "SJ14") (pin "P$2") (pinfunction "2_P$2") (pintype "passive"))
      (node (ref "SJ2") (pin "P$2") (pinfunction "2_P$2") (pintype "passive"))
      (node (ref "SJ5") (pin "P$2") (pinfunction "2_P$2") (pintype "passive"))
      (node (ref "SJ8") (pin "P$2") (pinfunction "2_P$2") (pintype "passive"))
      (node (ref "U$2") (pin "6") (pinfunction "VDD_6") (pintype "power_in"))
      (node (ref "U$3") (pin "6") (pinfunction "VDD_6") (pintype "power_in"))
      (node (ref "U$4") (pin "6") (pinfunction "VDD_6") (pintype "power_in"))
      (node (ref "U$5") (pin "6") (pinfunction "VDD_6") (pintype "power_in"))
      (node (ref "U8") (pin "1") (pinfunction "VIN_1") (pintype "bidirectional"))
      (node (ref "U8B") (pin "5") (pinfunction "IN_5") (pintype "input"))
    )
    (net (code "4") (name "/AGND") (class "Default")
      (node (ref "U$1") (pin "AGND") (pinfunction "AGND_AGND") (pintype "power_in"))
    )
    (net (code "5") (name "/AVDD") (class "Default")
      (node (ref "U$1") (pin "AVDD") (pinfunction "AVDD_AVDD") (pintype "power_in"))
    )
    (net (code "6") (name "/CANH") (class "Default")
      (node (ref "J1") (pin "1") (pinfunction "1_1") (pintype "passive"))
      (node (ref "J2") (pin "1") (pinfunction "1_1") (pintype "passive"))
      (node (ref "U7") (pin "7") (pinfunction "CANH_7") (pintype "bidirectional"))
      (node (ref "U7B") (pin "7") (pinfunction "CANH_7") (pintype "bidirectional"))
    )
    (net (code "7") (name "/CANL") (class "Default")
      (node (ref "J1") (pin "2") (pinfunction "2_2") (pintype "passive"))
      (node (ref "J2") (pin "2") (pinfunction "2_2") (pintype "passive"))
      (node (ref "U7") (pin "6") (pinfunction "CANL_6") (pintype "bidirectional"))
      (node (ref "U7B") (pin "6") (pinfunction "CANL_6") (pintype "bidirectional"))
    )
    (net (code "8") (name "/GND4") (class "Default")
      (node (ref "U$1") (pin "GND4") (pinfunction "GND4_GND4") (pintype "power_in"))
    )
    (net (code "9") (name "/PWR_POS") (class "Default")
      (node (ref "J1") (pin "8") (pinfunction "8_8") (pintype "passive"))
      (node (ref "J2") (pin "8") (pinfunction "8_8") (pintype "passive"))
      (node (ref "R40") (pin "1") (pinfunction "1_1") (pintype "passive"))
    )
    (net (code "10") (name "/U5V") (class "Default")
      (node (ref "U$1") (pin "U5V") (pinfunction "U5V_U5V") (pintype "power_in"))
    )
    (net (code "11") (name "/VBAT") (class "Default")
      (node (ref "U$1") (pin "VBAT") (pinfunction "VBAT_VBAT") (pintype "power_in"))
    )
    (net (code "12") (name "/VDD") (class "Default")
      (node (ref "U$1") (pin "VDD") (pinfunction "VDD_VDD") (pintype "power_in"))
    )
    (net (code "13") (name "CANRX") (class "Default")
      (node (ref "U$1") (pin "PB8") (pinfunction "PB8_PB8") (pintype "bidirectional"))
      (node (ref "U7") (pin "4") (pinfunction "RXD_4") (pintype "output"))
      (node (ref "U7B") (pin "4") (pinfunction "RXD_4") (pintype "bidirectional"))
    )
    (net (code "14") (name "CANTX") (class "Default")
      (node (ref "U$1") (pin "PB9") (pinfunction "PB9_PB9") (pintype "bidirectional"))
      (node (ref "U7") (pin "1") (pinfunction "TXD_1") (pintype "input"))
      (node (ref "U7B") (pin "1") (pinfunction "TXD_1") (pintype "bidirectional"))
    )
    (net (code "15") (name "E_CS") (class "Default")
      (node (ref "JP9") (pin "4") (pinfunction "4_4") (pintype "passive"))
      (node (ref "R23") (pin "2") (pinfunction "2_2") (pintype "passive"))
      (node (ref "U$1") (pin "PC10") (pinfunction "PC10_PC10") (pintype "bidirectional"))
    )
    (net (code "16") (name "E_LAT") (class "Default")
      (node (ref "JP10") (pin "1") (pinfunction "1_1") (pintype "passive"))
      (node (ref "R22") (pin "2") (pinfunction "2_2") (pintype "passive"))
      (node (ref "U$1") (pin "PC11") (pinfunction "PC11_PC11") (pintype "bidirectional"))
    )
    (net (code "17") (name "GND") (class "Default")
      (node (ref "C1") (pin "2") (pinfunction "2_2") (pintype "passive"))
      (node (ref "C10") (pin "2") (pinfunction "2_2") (pintype "passive"))
      (node (ref "C11") (pin "2") (pinfunction "2_2") (pintype "passive"))
      (node (ref "C2") (pin "-") (pinfunction "-_-") (pintype "passive"))
      (node (ref "C3") (pin "2") (pinfunction "2_2") (pintype "passive"))
      (node (ref "C4") (pin "2") (pinfunction "2_2") (pintype "passive"))
      (node (ref "C5") (pin "2") (pinfunction "2_2") (pintype "passive"))
      (node (ref "C6") (pin "2") (pinfunction "2_2") (pintype "passive"))
      (node (ref "C7") (pin "2") (pinfunction "2_2") (pintype "passive"))
      (node (ref "C8") (pin "2") (pinfunction "2_2") (pintype "passive"))
      (node (ref "C9") (pin "2") (pinfunction "2_2") (pintype "passive"))
      (node (ref "D1") (pin "A") (pinfunction "A_A") (pintype "passive"))
      (node (ref "IC1") (pin "6") (pinfunction "INH_6") (pintype "input"))
      (node (ref "IC1") (pin "8") (pinfunction "GND_8") (pintype "power_in"))
      (node (ref "IC3") (pin "13") (pinfunction "G_13") (pintype "input"))
      (node (ref "IC3") (pin "8") (pinfunction "GND_8") (pintype "power_in"))
      (node (ref "IC4") (pin "6") (pinfunction "INH_6") (pintype "input"))
      (node (ref "IC4") (pin "8") (pinfunction "GND_8") (pintype "power_in"))
      (node (ref "IC5") (pin "13") (pinfunction "G_13") (pintype "input"))
      (node (ref "IC5") (pin "8") (pinfunction "GND_8") (pintype "power_in"))
      (node (ref "IC6") (pin "11") (pinfunction "V-_11") (pintype "power_in"))
      (node (ref "IC9") (pin "11") (pinfunction "V-_11") (pintype "power_in"))
      (node (ref "J1") (pin "3") (pinfunction "3_3") (pintype "passive"))
      (node (ref "J1") (pin "6") (pinfunction "6_6") (pintype "passive"))
      (node (ref "J1") (pin "7") (pinfunction "7_7") (pintype "passive"))
      (node (ref "J2") (pin "3") (pinfunction "3_3") (pintype "passive"))
      (node (ref "J2") (pin "6") (pinfunction "6_6") (pintype "passive"))
      (node (ref "J2") (pin "7") (pinfunction "7_7") (pintype "passive"))
      (node (ref "J3") (pin "2") (pinfunction "2_2") (pintype "passive"))
      (node (ref "J3") (pin "3") (pinfunction "3_3") (pintype "passive"))
      (node (ref "JP10") (pin "4") (pinfunction "4_4") (pintype "passive"))
      (node (ref "JP11") (pin "5") (pinfunction "5_5") (pintype "passive"))
      (node (ref "JP11") (pin "6") (pinfunction "6_6") (pintype "passive"))
      (node (ref "JP12") (pin "5") (pinfunction "5_5") (pintype "passive"))
      (node (ref "JP12") (pin "6") (pinfunction "6_6") (pintype "passive"))
      (node (ref "JP13") (pin "5") (pinfunction "5_5") (pintype "passive"))
      (node (ref "JP14") (pin "5") (pinfunction "5_5") (pintype "passive"))
      (node (ref "JP15") (pin "5") (pinfunction "5_5") (pintype "passive"))
      (node (ref "JP16") (pin "5") (pinfunction "5_5") (pintype "passive"))
      (node (ref "JP16") (pin "6") (pinfunction "6_6") (pintype "passive"))
      (node (ref "JP7") (pin "5") (pinfunction "5_5") (pintype "passive"))
      (node (ref "JP7") (pin "6") (pinfunction "6_6") (pintype "passive"))
      (node (ref "JP8") (pin "4") (pinfunction "4_4") (pintype "passive"))
      (node (ref "Q1") (pin "2") (pinfunction "S_2") (pintype "passive"))
      (node (ref "Q10") (pin "2") (pinfunction "S_2") (pintype "passive"))
      (node (ref "Q11") (pin "2") (pinfunction "S_2") (pintype "passive"))
      (node (ref "Q12") (pin "2") (pinfunction "S_2") (pintype "passive"))
      (node (ref "Q13") (pin "2") (pinfunction "S_2") (pintype "passive"))
      (node (ref "Q14") (pin "2") (pinfunction "S_2") (pintype "passive"))
      (node (ref "Q15") (pin "2") (pinfunction "S_2") (pintype "passive"))
      (node (ref "Q16") (pin "2") (pinfunction "S_2") (pintype "passive"))
      (node (ref "Q2") (pin "2") (pinfunction "S_2") (pintype "passive"))
      (node (ref "Q3") (pin "2") (pinfunction "S_2") (pintype "passive"))
      (node (ref "Q4") (pin "2") (pinfunction "S_2") (pintype "passive"))
      (node (ref "Q5") (pin "2") (pinfunction "S_2") (pintype "passive"))
      (node (ref "Q6") (pin "2") (pinfunction "S_2") (pintype "passive"))
      (node (ref "Q7") (pin "2") (pinfunction "S_2") (pintype "passive"))
      (node (ref "Q8") (pin "2") (pinfunction "S_2") (pintype "passive"))
      (node (ref "Q9") (pin "2") (pinfunction "S_2") (pintype "passive"))
      (node (ref "R2") (pin "1") (pinfunction "1_1") (pintype "passive"))
      (node (ref "R61") (pin "2") (pinfunction "2_2") (pintype "passive"))
      (node (ref "SJ12") (pin "P$2") (pinfunction "2_P$2") (pintype "passive"))
      (node (ref "SJ3") (pin "2") (pinfunction "2_2") (pintype "passive"))
      (node (ref "SJ6") (pin "P$2") (pinfunction "2_P$2") (pintype "passive"))
      (node (ref "SJ9") (pin "2") (pinfunction "2_2") (pintype "passive"))
      (node (ref "U$1") (pin "GND3") (pinfunction "GND3_GND3") (pintype "power_in"))
      (node (ref "U$1") (pin "GND5") (pinfunction "GND5_GND5") (pintype "power_in"))
      (node (ref "U$1") (pin "GND6") (pinfunction "GND6_GND6") (pintype "power_in"))
      (node (ref "U$1") (pin "GND7") (pinfunction "GND7_GND7") (pintype "power_in"))
      (node (ref "U$1") (pin "GND8") (pinfunction "GND8_GND8") (pintype "power_in"))
      (node (ref "U$2") (pin "3") (pinfunction "VSS_3") (pintype "power_in"))
      (node (ref "U$3") (pin "3") (pinfunction "VSS_3") (pintype "power_in"))
      (node (ref "U$4") (pin "3") (pinfunction "VSS_3") (pintype "power_in"))
      (node (ref "U$5") (pin "3") (pinfunction "VSS_3") (pintype "power_in"))
      (node (ref "U7") (pin "2") (pinfunction "GND_2") (pintype "power_in"))
      (node (ref "U7B") (pin "2") (pinfunction "VSS_2") (pintype "power_in"))
      (node (ref "U8") (pin "4") (pinfunction "SD_4") (pintype "bidirectional"))
      (node (ref "U8") (pin "5") (pinfunction "GND1_5") (pintype "power_in"))
      (node (ref "U8") (pin "6") (pinfunction "GND2_6") (pintype "power_in"))
      (node (ref "U8") (pin "7") (pinfunction "GND3_7") (pintype "power_in"))
      (node (ref "U8") (pin "8") (pinfunction "GND4_8") (pintype "power_in"))
      (node (ref "U8B") (pin "2") (pinfunction "GNDSIG_2") (pintype "input"))
      (node (ref "U8B") (pin "3") (pinfunction "~{ON/OFF}_3") (pintype "input"))
      (node (ref "U8B") (pin "4") (pinfunction "GND_4") (pintype "power_in"))
      (node (ref "X1") (pin "2") (pinfunction "2_2") (pintype "passive"))
    )
    (net (code "18") (name "I2CSCL") (class "Default")
      (node (ref "JP8") (pin "2") (pinfunction "2_2") (pintype "passive"))
      (node (ref "R63") (pin "2") (pinfunction "2_2") (pintype "passive"))
      (node (ref "U$1") (pin "PB6") (pinfunction "PB6_PB6") (pintype "bidirectional"))
    )
    (net (code "19") (name "I2CSDA") (class "Default")
      (node (ref "JP8") (pin "1") (pinfunction "1_1") (pintype "passive"))
      (node (ref "R62") (pin "2") (pinfunction "2_2") (pintype "passive"))
      (node (ref "U$1") (pin "PB7") (pinfunction "PB7_PB7") (pintype "bidirectional"))
    )
    (net (code "20") (name "ILAT") (class "Default")
      (node (ref "IC1") (pin "15") (pinfunction "SH/~{LD}_15") (pintype "input"))
      (node (ref "IC4") (pin "15") (pinfunction "SH/~{LD}_15") (pintype "input"))
      (node (ref "U$1") (pin "PA6") (pinfunction "PA6_PA6") (pintype "bidirectional"))
    )
    (net (code "21") (name "MISO") (class "Default")
      (node (ref "JP9") (pin "1") (pinfunction "1_1") (pintype "passive"))
      (node (ref "U$1") (pin "PB4") (pinfunction "PB4_PB4") (pintype "bidirectional"))
    )
    (net (code "22") (name "MISO2") (class "Default")
      (node (ref "IC4") (pin "13") (pinfunction "QH_13") (pintype "output"))
      (node (ref "SJ13") (pin "P$2") (pinfunction "2_P$2") (pintype "passive"))
      (node (ref "U$1") (pin "PC2") (pinfunction "PC2_PC2") (pintype "bidirectional"))
    )
    (net (code "23") (name "MOSI") (class "Default")
      (node (ref "IC5") (pin "14") (pinfunction "SER_14") (pintype "input"))
      (node (ref "R20") (pin "1") (pinfunction "1_1") (pintype "passive"))
      (node (ref "SJ15") (pin "1") (pinfunction "1_1") (pintype "passive"))
      (node (ref "SJ17") (pin "P$2") (pinfunction "2_P$2") (pintype "passive"))
      (node (ref "U$1") (pin "PB5") (pinfunction "PB5_PB5") (pintype "bidirectional"))
    )
    (net (code "24") (name "Net-(D2-PadA)") (class "Default")
      (node (ref "D2") (pin "A") (pinfunction "A_A") (pintype "passive"))
      (node (ref "JP4") (pin "4") (pinfunction "4_4") (pintype "passive"))
    )
    (net (code "25") (name "Net-(D2-PadC)") (class "Default")
      (node (ref "D2") (pin "C") (pinfunction "C_C") (pintype "passive"))
      (node (ref "JP4") (pin "1") (pinfunction "1_1") (pintype "passive"))
    )
    (net (code "26") (name "Net-(IC1A-A)") (class "Default")
      (node (ref "IC1") (pin "2") (pinfunction "A_2") (pintype "input"))
      (node (ref "R36") (pin "1") (pinfunction "1_1") (pintype "passive"))
      (node (ref "RN3") (pin "9") (pinfunction "2_9") (pintype "passive"))
    )
    (net (code "27") (name "Net-(IC1A-B)") (class "Default")
      (node (ref "IC1") (pin "3") (pinfunction "B_3") (pintype "input"))
      (node (ref "R37") (pin "1") (pinfunction "1_1") (pintype "passive"))
      (node (ref "RN3") (pin "10") (pinfunction "2_10") (pintype "passive"))
    )
    (net (code "28") (name "Net-(IC1A-C)") (class "Default")
      (node (ref "IC1") (pin "4") (pinfunction "C_4") (pintype "input"))
      (node (ref "R38") (pin "1") (pinfunction "1_1") (pintype "passive"))
      (node (ref "RN3") (pin "11") (pinfunction "2_11") (pintype "passive"))
    )
    (net (code "29") (name "Net-(IC1A-D)") (class "Default")
      (node (ref "IC1") (pin "5") (pinfunction "D_5") (pintype "input"))
      (node (ref "R39") (pin "1") (pinfunction "1_1") (pintype "passive"))
      (node (ref "RN3") (pin "12") (pinfunction "2_12") (pintype "passive"))
    )
    (net (code "30") (name "Net-(IC1A-E)") (class "Default")
      (node (ref "IC1") (pin "10") (pinfunction "E_10") (pintype "input"))
      (node (ref "R41") (pin "1") (pinfunction "1_1") (pintype "passive"))
      (node (ref "RN3") (pin "13") (pinfunction "2_13") (pintype "passive"))
    )
    (net (code "31") (name "Net-(IC1A-F)") (class "Default")
      (node (ref "IC1") (pin "11") (pinfunction "F_11") (pintype "input"))
      (node (ref "R42") (pin "1") (pinfunction "1_1") (pintype "passive"))
      (node (ref "RN3") (pin "14") (pinfunction "2_14") (pintype "passive"))
    )
    (net (code "32") (name "Net-(IC1A-G)") (class "Default")
      (node (ref "IC1") (pin "12") (pinfunction "G_12") (pintype "input"))
      (node (ref "R43") (pin "1") (pinfunction "1_1") (pintype "passive"))
      (node (ref "RN3") (pin "15") (pinfunction "2_15") (pintype "passive"))
    )
    (net (code "33") (name "Net-(IC1A-H)") (class "Default")
      (node (ref "IC1") (pin "14") (pinfunction "H_14") (pintype "input"))
      (node (ref "R44") (pin "1") (pinfunction "1_1") (pintype "passive"))
      (node (ref "RN3") (pin "16") (pinfunction "2_16") (pintype "passive"))
    )
    (net (code "34") (name "Net-(IC2-CD+)") (class "Default")
      (node (ref "IC2") (pin "10") (pinfunction "CD+_10") (pintype "passive"))
      (node (ref "SJ4") (pin "P$1") (pinfunction "1_P$1") (pintype "passive"))
      (node (ref "SJ5") (pin "P$1") (pinfunction "1_P$1") (pintype "passive"))
      (node (ref "SJ6") (pin "P$1") (pinfunction "1_P$1") (pintype "passive"))
    )
    (net (code "35") (name "Net-(IC2-GND)") (class "Default")
      (node (ref "IC2") (pin "9") (pinfunction "GND_9") (pintype "power_in"))
      (node (ref "SJ1") (pin "P$1") (pinfunction "1_P$1") (pintype "passive"))
      (node (ref "SJ2") (pin "P$1") (pinfunction "1_P$1") (pintype "passive"))
      (node (ref "SJ3") (pin "1") (pinfunction "1_1") (pintype "passive"))
    )
    (net (code "36") (name "Net-(IC2-I1)") (class "Default")
      (node (ref "IC2") (pin "1") (pinfunction "I1_1") (pintype "input"))
      (node (ref "IC5") (pin "15") (pinfunction "QA_15") (pintype "tri_state"))
      (node (ref "R3") (pin "1") (pinfunction "1_1") (pintype "passive"))
    )
    (net (code "37") (name "Net-(IC2-I2)") (class "Default")
      (node (ref "IC2") (pin "2") (pinfunction "I2_2") (pintype "input"))
      (node (ref "IC5") (pin "1") (pinfunction "QB_1") (pintype "tri_state"))
      (node (ref "R4") (pin "1") (pinfunction "1_1") (pintype "passive"))
    )
    (net (code "38") (name "Net-(IC2-I3)") (class "Default")
      (node (ref "IC2") (pin "3") (pinfunction "I3_3") (pintype "input"))
      (node (ref "IC5") (pin "2") (pinfunction "QC_2") (pintype "tri_state"))
      (node (ref "R5") (pin "1") (pinfunction "1_1") (pintype "passive"))
    )
    (net (code "39") (name "Net-(IC2-I4)") (class "Default")
      (node (ref "IC2") (pin "4") (pinfunction "I4_4") (pintype "input"))
      (node (ref "IC5") (pin "3") (pinfunction "QD_3") (pintype "tri_state"))
      (node (ref "R6") (pin "1") (pinfunction "1_1") (pintype "passive"))
    )
    (net (code "40") (name "Net-(IC2-I5)") (class "Default")
      (node (ref "IC2") (pin "5") (pinfunction "I5_5") (pintype "input"))
      (node (ref "IC5") (pin "4") (pinfunction "QE_4") (pintype "tri_state"))
      (node (ref "R7") (pin "1") (pinfunction "1_1") (pintype "passive"))
    )
    (net (code "41") (name "Net-(IC2-I6)") (class "Default")
      (node (ref "IC2") (pin "6") (pinfunction "I6_6") (pintype "input"))
      (node (ref "IC5") (pin "5") (pinfunction "QF_5") (pintype "tri_state"))
      (node (ref "R8") (pin "1") (pinfunction "1_1") (pintype "passive"))
    )
    (net (code "42") (name "Net-(IC2-I7)") (class "Default")
      (node (ref "IC2") (pin "7") (pinfunction "I7_7") (pintype "input"))
      (node (ref "IC5") (pin "6") (pinfunction "QG_6") (pintype "tri_state"))
      (node (ref "R9") (pin "1") (pinfunction "1_1") (pintype "passive"))
    )
    (net (code "43") (name "Net-(IC2-I8)") (class "Default")
      (node (ref "IC2") (pin "8") (pinfunction "I8_8") (pintype "input"))
      (node (ref "IC5") (pin "7") (pinfunction "QH_7") (pintype "tri_state"))
      (node (ref "R10") (pin "1") (pinfunction "1_1") (pintype "passive"))
    )
    (net (code "44") (name "Net-(IC2-O1)") (class "Default")
      (node (ref "IC2") (pin "18") (pinfunction "O1_18") (pintype "open_collector"))
      (node (ref "JP1") (pin "1") (pinfunction "1_1") (pintype "passive"))
      (node (ref "Q1") (pin "3") (pinfunction "D_3") (pintype "passive"))
    )
    (net (code "45") (name "Net-(IC2-O2)") (class "Default")
      (node (ref "IC2") (pin "17") (pinfunction "O2_17") (pintype "open_collector"))
      (node (ref "JP1") (pin "2") (pinfunction "2_2") (pintype "passive"))
      (node (ref "Q2") (pin "3") (pinfunction "D_3") (pintype "passive"))
    )
    (net (code "46") (name "Net-(IC2-O3)") (class "Default")
      (node (ref "IC2") (pin "16") (pinfunction "O3_16") (pintype "open_collector"))
      (node (ref "JP1") (pin "3") (pinfunction "3_3") (pintype "passive"))
      (node (ref "Q3") (pin "3") (pinfunction "D_3") (pintype "passive"))
    )
    (net (code "47") (name "Net-(IC2-O4)") (class "Default")
      (node (ref "IC2") (pin "15") (pinfunction "O4_15") (pintype "open_collector"))
      (node (ref "JP1") (pin "4") (pinfunction "4_4") (pintype "passive"))
      (node (ref "Q4") (pin "3") (pinfunction "D_3") (pintype "passive"))
    )
    (net (code "48") (name "Net-(IC2-O5)") (class "Default")
      (node (ref "IC2") (pin "14") (pinfunction "O5_14") (pintype "open_collector"))
      (node (ref "JP1") (pin "5") (pinfunction "5_5") (pintype "passive"))
      (node (ref "Q5") (pin "3") (pinfunction "D_3") (pintype "passive"))
    )
    (net (code "49") (name "Net-(IC2-O6)") (class "Default")
      (node (ref "IC2") (pin "13") (pinfunction "O6_13") (pintype "open_collector"))
      (node (ref "JP1") (pin "6") (pinfunction "6_6") (pintype "passive"))
      (node (ref "Q6") (pin "3") (pinfunction "D_3") (pintype "passive"))
    )
    (net (code "50") (name "Net-(IC2-O7)") (class "Default")
      (node (ref "IC2") (pin "12") (pinfunction "O7_12") (pintype "open_collector"))
      (node (ref "JP1") (pin "7") (pinfunction "7_7") (pintype "passive"))
      (node (ref "Q7") (pin "3") (pinfunction "D_3") (pintype "passive"))
    )
    (net (code "51") (name "Net-(IC2-O8)") (class "Default")
      (node (ref "IC2") (pin "11") (pinfunction "O8_11") (pintype "open_collector"))
      (node (ref "JP1") (pin "8") (pinfunction "8_8") (pintype "passive"))
      (node (ref "Q8") (pin "3") (pinfunction "D_3") (pintype "passive"))
    )
    (net (code "52") (name "Net-(IC3A-QA)") (class "Default")
      (node (ref "IC3") (pin "15") (pinfunction "QA_15") (pintype "tri_state"))
      (node (ref "IC8") (pin "1") (pinfunction "I1_1") (pintype "input"))
      (node (ref "R11") (pin "1") (pinfunction "1_1") (pintype "passive"))
    )
    (net (code "53") (name "Net-(IC3A-QB)") (class "Default")
      (node (ref "IC3") (pin "1") (pinfunction "QB_1") (pintype "tri_state"))
      (node (ref "IC8") (pin "2") (pinfunction "I2_2") (pintype "input"))
      (node (ref "R12") (pin "1") (pinfunction "1_1") (pintype "passive"))
    )
    (net (code "54") (name "Net-(IC3A-QC)") (class "Default")
      (node (ref "IC3") (pin "2") (pinfunction "QC_2") (pintype "tri_state"))
      (node (ref "IC8") (pin "3") (pinfunction "I3_3") (pintype "input"))
      (node (ref "R13") (pin "1") (pinfunction "1_1") (pintype "passive"))
    )
    (net (code "55") (name "Net-(IC3A-QD)") (class "Default")
      (node (ref "IC3") (pin "3") (pinfunction "QD_3") (pintype "tri_state"))
      (node (ref "IC8") (pin "4") (pinfunction "I4_4") (pintype "input"))
      (node (ref "R14") (pin "1") (pinfunction "1_1") (pintype "passive"))
    )
    (net (code "56") (name "Net-(IC3A-QE)") (class "Default")
      (node (ref "IC3") (pin "4") (pinfunction "QE_4") (pintype "tri_state"))
      (node (ref "IC8") (pin "5") (pinfunction "I5_5") (pintype "input"))
      (node (ref "R15") (pin "1") (pinfunction "1_1") (pintype "passive"))
    )
    (net (code "57") (name "Net-(IC3A-QF)") (class "Default")
      (node (ref "IC3") (pin "5") (pinfunction "QF_5") (pintype "tri_state"))
      (node (ref "IC8") (pin "6") (pinfunction "I6_6") (pintype "input"))
      (node (ref "R16") (pin "1") (pinfunction "1_1") (pintype "passive"))
    )
    (net (code "58") (name "Net-(IC3A-QG)") (class "Default")
      (node (ref "IC3") (pin "6") (pinfunction "QG_6") (pintype "tri_state"))
      (node (ref "IC8") (pin "7") (pinfunction "I7_7") (pintype "input"))
      (node (ref "R17") (pin "1") (pinfunction "1_1") (pintype "passive"))
    )
    (net (code "59") (name "Net-(IC3A-QH)") (class "Default")
      (node (ref "IC3") (pin "7") (pinfunction "QH_7") (pintype "tri_state"))
      (node (ref "IC8") (pin "8") (pinfunction "I8_8") (pintype "input"))
      (node (ref "R18") (pin "1") (pinfunction "1_1") (pintype "passive"))
    )
    (net (code "60") (name "Net-(IC4A-A)") (class "Default")
      (node (ref "IC4") (pin "2") (pinfunction "A_2") (pintype "input"))
      (node (ref "R28") (pin "1") (pinfunction "1_1") (pintype "passive"))
      (node (ref "RN1") (pin "9") (pinfunction "2_9") (pintype "passive"))
    )
    (net (code "61") (name "Net-(IC4A-B)") (class "Default")
      (node (ref "IC4") (pin "3") (pinfunction "B_3") (pintype "input"))
      (node (ref "R29") (pin "1") (pinfunction "1_1") (pintype "passive"))
      (node (ref "RN1") (pin "10") (pinfunction "2_10") (pintype "passive"))
    )
    (net (code "62") (name "Net-(IC4A-C)") (class "Default")
      (node (ref "IC4") (pin "4") (pinfunction "C_4") (pintype "input"))
      (node (ref "R30") (pin "1") (pinfunction "1_1") (pintype "passive"))
      (node (ref "RN1") (pin "11") (pinfunction "2_11") (pintype "passive"))
    )
    (net (code "63") (name "Net-(IC4A-D)") (class "Default")
      (node (ref "IC4") (pin "5") (pinfunction "D_5") (pintype "input"))
      (node (ref "R31") (pin "1") (pinfunction "1_1") (pintype "passive"))
      (node (ref "RN1") (pin "12") (pinfunction "2_12") (pintype "passive"))
    )
    (net (code "64") (name "Net-(IC4A-E)") (class "Default")
      (node (ref "IC4") (pin "10") (pinfunction "E_10") (pintype "input"))
      (node (ref "R32") (pin "1") (pinfunction "1_1") (pintype "passive"))
      (node (ref "RN1") (pin "13") (pinfunction "2_13") (pintype "passive"))
    )
    (net (code "65") (name "Net-(IC4A-F)") (class "Default")
      (node (ref "IC4") (pin "11") (pinfunction "F_11") (pintype "input"))
      (node (ref "R33") (pin "1") (pinfunction "1_1") (pintype "passive"))
      (node (ref "RN1") (pin "14") (pinfunction "2_14") (pintype "passive"))
    )
    (net (code "66") (name "Net-(IC4A-G)") (class "Default")
      (node (ref "IC4") (pin "12") (pinfunction "G_12") (pintype "input"))
      (node (ref "R34") (pin "1") (pinfunction "1_1") (pintype "passive"))
      (node (ref "RN1") (pin "15") (pinfunction "2_15") (pintype "passive"))
    )
    (net (code "67") (name "Net-(IC4A-H)") (class "Default")
      (node (ref "IC4") (pin "14") (pinfunction "H_14") (pintype "input"))
      (node (ref "R35") (pin "1") (pinfunction "1_1") (pintype "passive"))
      (node (ref "RN1") (pin "16") (pinfunction "2_16") (pintype "passive"))
    )
    (net (code "68") (name "Net-(IC6A--IN)") (class "Default")
      (node (ref "IC6") (pin "13") (pinfunction "-IN_13") (pintype "input"))
      (node (ref "IC6") (pin "2") (pinfunction "-IN_2") (pintype "input"))
      (node (ref "IC6") (pin "6") (pinfunction "-IN_6") (pintype "input"))
      (node (ref "IC6") (pin "9") (pinfunction "-IN_9") (pintype "input"))
      (node (ref "IC9") (pin "13") (pinfunction "-IN_13") (pintype "input"))
      (node (ref "IC9") (pin "2") (pinfunction "-IN_2") (pintype "input"))
      (node (ref "IC9") (pin "6") (pinfunction "-IN_6") (pintype "input"))
      (node (ref "IC9") (pin "9") (pinfunction "-IN_9") (pintype "input"))
      (node (ref "R1") (pin "1") (pinfunction "1_1") (pintype "passive"))
      (node (ref "R2") (pin "2") (pinfunction "2_2") (pintype "passive"))
    )
    (net (code "69") (name "Net-(IC6A-OUT)") (class "Default")
      (node (ref "IC6") (pin "1") (pinfunction "OUT_1") (pintype "output"))
      (node (ref "JP15") (pin "3") (pinfunction "3_3") (pintype "passive"))
      (node (ref "JP5") (pin "3") (pinfunction "3_3") (pintype "passive"))
      (node (ref "U$5") (pin "5") (pinfunction "O_5") (pintype "output"))
    )
    (net (code "70") (name "Net-(IC6B-OUT)") (class "Default")
      (node (ref "IC6") (pin "7") (pinfunction "OUT_7") (pintype "output"))
      (node (ref "JP15") (pin "1") (pinfunction "1_1") (pintype "passive"))
      (node (ref "JP5") (pin "1") (pinfunction "1_1") (pintype "passive"))
      (node (ref "U$4") (pin "7") (pinfunction "O_7") (pintype "output"))
    )
    (net (code "71") (name "Net-(IC6C-OUT)") (class "Default")
      (node (ref "IC6") (pin "8") (pinfunction "OUT_8") (pintype "output"))
      (node (ref "JP15") (pin "2") (pinfunction "2_2") (pintype "passive"))
      (node (ref "JP5") (pin "2") (pinfunction "2_2") (pintype "passive"))
      (node (ref "U$4") (pin "5") (pinfunction "O_5") (pintype "output"))
    )
    (net (code "72") (name "Net-(IC6D-OUT)") (class "Default")
      (node (ref "IC6") (pin "14") (pinfunction "OUT_14") (pintype "output"))
      (node (ref "JP15") (pin "4") (pinfunction "4_4") (pintype "passive"))
      (node (ref "JP5") (pin "4") (pinfunction "4_4") (pintype "passive"))
      (node (ref "U$5") (pin "7") (pinfunction "O_7") (pintype "output"))
    )
    (net (code "73") (name "Net-(IC8-CD+)") (class "Default")
      (node (ref "IC8") (pin "10") (pinfunction "CD+_10") (pintype "passive"))
      (node (ref "SJ10") (pin "P$1") (pinfunction "1_P$1") (pintype "passive"))
      (node (ref "SJ11") (pin "P$1") (pinfunction "1_P$1") (pintype "passive"))
      (node (ref "SJ12") (pin "P$1") (pinfunction "1_P$1") (pintype "passive"))
    )
    (net (code "74") (name "Net-(IC8-GND)") (class "Default")
      (node (ref "IC8") (pin "9") (pinfunction "GND_9") (pintype "power_in"))
      (node (ref "SJ7") (pin "P$1") (pinfunction "1_P$1") (pintype "passive"))
      (node (ref "SJ8") (pin "P$1") (pinfunction "1_P$1") (pintype "passive"))
      (node (ref "SJ9") (pin "1") (pinfunction "1_1") (pintype "passive"))
    )
    (net (code "75") (name "Net-(IC8-O1)") (class "Default")
      (node (ref "IC8") (pin "18") (pinfunction "O1_18") (pintype "open_collector"))
      (node (ref "JP6") (pin "1") (pinfunction "1_1") (pintype "passive"))
      (node (ref "Q9") (pin "3") (pinfunction "D_3") (pintype "passive"))
    )
    (net (code "76") (name "Net-(IC8-O2)") (class "Default")
      (node (ref "IC8") (pin "17") (pinfunction "O2_17") (pintype "open_collector"))
      (node (ref "JP6") (pin "2") (pinfunction "2_2") (pintype "passive"))
      (node (ref "Q10") (pin "3") (pinfunction "D_3") (pintype "passive"))
    )
    (net (code "77") (name "Net-(IC8-O3)") (class "Default")
      (node (ref "IC8") (pin "16") (pinfunction "O3_16") (pintype "open_collector"))
      (node (ref "JP6") (pin "3") (pinfunction "3_3") (pintype "passive"))
      (node (ref "Q11") (pin "3") (pinfunction "D_3") (pintype "passive"))
    )
    (net (code "78") (name "Net-(IC8-O4)") (class "Default")
      (node (ref "IC8") (pin "15") (pinfunction "O4_15") (pintype "open_collector"))
      (node (ref "JP6") (pin "4") (pinfunction "4_4") (pintype "passive"))
      (node (ref "Q12") (pin "3") (pinfunction "D_3") (pintype "passive"))
    )
    (net (code "79") (name "Net-(IC8-O5)") (class "Default")
      (node (ref "IC8") (pin "14") (pinfunction "O5_14") (pintype "open_collector"))
      (node (ref "JP6") (pin "5") (pinfunction "5_5") (pintype "passive"))
      (node (ref "Q13") (pin "3") (pinfunction "D_3") (pintype "passive"))
    )
    (net (code "80") (name "Net-(IC8-O6)") (class "Default")
      (node (ref "IC8") (pin "13") (pinfunction "O6_13") (pintype "open_collector"))
      (node (ref "JP6") (pin "6") (pinfunction "6_6") (pintype "passive"))
      (node (ref "Q14") (pin "3") (pinfunction "D_3") (pintype "passive"))
    )
    (net (code "81") (name "Net-(IC8-O7)") (class "Default")
      (node (ref "IC8") (pin "12") (pinfunction "O7_12") (pintype "open_collector"))
      (node (ref "JP6") (pin "7") (pinfunction "7_7") (pintype "passive"))
      (node (ref "Q15") (pin "3") (pinfunction "D_3") (pintype "passive"))
    )
    (net (code "82") (name "Net-(IC8-O8)") (class "Default")
      (node (ref "IC8") (pin "11") (pinfunction "O8_11") (pintype "open_collector"))
      (node (ref "JP6") (pin "8") (pinfunction "8_8") (pintype "passive"))
      (node (ref "Q16") (pin "3") (pinfunction "D_3") (pintype "passive"))
    )
    (net (code "83") (name "Net-(IC9A-OUT)") (class "Default")
      (node (ref "IC9") (pin "1") (pinfunction "OUT_1") (pintype "output"))
      (node (ref "JP15") (pin "9") (pinfunction "9_9") (pintype "passive"))
      (node (ref "JP5") (pin "7") (pinfunction "7_7") (pintype "passive"))
      (node (ref "U$3") (pin "5") (pinfunction "O_5") (pintype "output"))
    )
    (net (code "84") (name "Net-(IC9B-OUT)") (class "Default")
      (node (ref "IC9") (pin "7") (pinfunction "OUT_7") (pintype "output"))
      (node (ref "JP15") (pin "7") (pinfunction "7_7") (pintype "passive"))
      (node (ref "JP5") (pin "5") (pinfunction "5_5") (pintype "passive"))
      (node (ref "U$2") (pin "7") (pinfunction "O_7") (pintype "output"))
    )
    (net (code "85") (name "Net-(IC9C-OUT)") (class "Default")
      (node (ref "IC9") (pin "8") (pinfunction "OUT_8") (pintype "output"))
      (node (ref "JP15") (pin "8") (pinfunction "8_8") (pintype "passive"))
      (node (ref "JP5") (pin "6") (pinfunction "6_6") (pintype "passive"))
      (node (ref "U$2") (pin "5") (pinfunction "O_5") (pintype "output"))
    )
    (net (code "86") (name "Net-(IC9D-OUT)") (class "Default")
      (node (ref "IC9") (pin "14") (pinfunction "OUT_14") (pintype "output"))
      (node (ref "JP15") (pin "10") (pinfunction "10_10") (pintype "passive"))
      (node (ref "JP5") (pin "8") (pinfunction "8_8") (pintype "passive"))
      (node (ref "U$3") (pin "7") (pinfunction "O_7") (pintype "output"))
    )
    (net (code "87") (name "Net-(J1-Pad4)") (class "Default")
      (node (ref "J1") (pin "4") (pinfunction "4_4") (pintype "passive"))
      (node (ref "J2") (pin "4") (pinfunction "4_4") (pintype "passive"))
    )
    (net (code "88") (name "Net-(J1-Pad5)") (class "Default")
      (node (ref "J1") (pin "5") (pinfunction "5_5") (pintype "passive"))
      (node (ref "J2") (pin "5") (pinfunction "5_5") (pintype "passive"))
    )
    (net (code "89") (name "Net-(JP4-Pad3)") (class "Default")
      (node (ref "JP4") (pin "3") (pinfunction "3_3") (pintype "passive"))
      (node (ref "R40") (pin "2") (pinfunction "2_2") (pintype "passive"))
    )
    (net (code "90") (name "Net-(JP13-Pad1)") (class "Default")
      (node (ref "JP13") (pin "1") (pinfunction "1_1") (pintype "passive"))
      (node (ref "JP3") (pin "1") (pinfunction "1_1") (pintype "passive"))
      (node (ref "R44") (pin "2") (pinfunction "2_2") (pintype "passive"))
      (node (ref "R53") (pin "2") (pinfunction "2_2") (pintype "passive"))
      (node (ref "RN3") (pin "1") (pinfunction "1_1") (pintype "passive"))
      (node (ref "RN4") (pin "9") (pinfunction "9_9") (pintype "passive"))
    )
    (net (code "91") (name "Net-(JP14-Pad1)") (class "Default")
      (node (ref "JP14") (pin "1") (pinfunction "1_1") (pintype "passive"))
      (node (ref "JP2") (pin "1") (pinfunction "1_1") (pintype "passive"))
      (node (ref "R35") (pin "2") (pinfunction "2_2") (pintype "passive"))
      (node (ref "R45") (pin "2") (pinfunction "2_2") (pintype "passive"))
      (node (ref "RN1") (pin "1") (pinfunction "1_1") (pintype "passive"))
      (node (ref "RN2") (pin "9") (pinfunction "9_9") (pintype "passive"))
    )
    (net (code "92") (name "Net-(Q1-G)") (class "Default")
      (node (ref "Q1") (pin "1") (pinfunction "G_1") (pintype "passive"))
      (node (ref "R3") (pin "2") (pinfunction "2_2") (pintype "passive"))
    )
    (net (code "93") (name "Net-(Q2-G)") (class "Default")
      (node (ref "Q2") (pin "1") (pinfunction "G_1") (pintype "passive"))
      (node (ref "R4") (pin "2") (pinfunction "2_2") (pintype "passive"))
    )
    (net (code "94") (name "Net-(Q3-G)") (class "Default")
      (node (ref "Q3") (pin "1") (pinfunction "G_1") (pintype "passive"))
      (node (ref "R5") (pin "2") (pinfunction "2_2") (pintype "passive"))
    )
    (net (code "95") (name "Net-(Q4-G)") (class "Default")
      (node (ref "Q4") (pin "1") (pinfunction "G_1") (pintype "passive"))
      (node (ref "R6") (pin "2") (pinfunction "2_2") (pintype "passive"))
    )
    (net (code "96") (name "Net-(Q5-G)") (class "Default")
      (node (ref "Q5") (pin "1") (pinfunction "G_1") (pintype "passive"))
      (node (ref "R7") (pin "2") (pinfunction "2_2") (pintype "passive"))
    )
    (net (code "97") (name "Net-(Q6-G)") (class "Default")
      (node (ref "Q6") (pin "1") (pinfunction "G_1") (pintype "passive"))
      (node (ref "R8") (pin "2") (pinfunction "2_2") (pintype "passive"))
    )
    (net (code "98") (name "Net-(Q7-G)") (class "Default")
      (node (ref "Q7") (pin "1") (pinfunction "G_1") (pintype "passive"))
      (node (ref "R9") (pin "2") (pinfunction "2_2") (pintype "passive"))
    )
    (net (code "99") (name "Net-(Q8-G)") (class "Default")
      (node (ref "Q8") (pin "1") (pinfunction "G_1") (pintype "passive"))
      (node (ref "R10") (pin "2") (pinfunction "2_2") (pintype "passive"))
    )
    (net (code "100") (name "Net-(Q9-G)") (class "Default")
      (node (ref "Q9") (pin "1") (pinfunction "G_1") (pintype "passive"))
      (node (ref "R11") (pin "2") (pinfunction "2_2") (pintype "passive"))
    )
    (net (code "101") (name "Net-(Q10-G)") (class "Default")
      (node (ref "Q10") (pin "1") (pinfunction "G_1") (pintype "passive"))
      (node (ref "R12") (pin "2") (pinfunction "2_2") (pintype "passive"))
    )
    (net (code "102") (name "Net-(Q11-G)") (class "Default")
      (node (ref "Q11") (pin "1") (pinfunction "G_1") (pintype "passive"))
      (node (ref "R13") (pin "2") (pinfunction "2_2") (pintype "passive"))
    )
    (net (code "103") (name "Net-(Q12-G)") (class "Default")
      (node (ref "Q12") (pin "1") (pinfunction "G_1") (pintype "passive"))
      (node (ref "R14") (pin "2") (pinfunction "2_2") (pintype "passive"))
    )
    (net (code "104") (name "Net-(Q13-G)") (class "Default")
      (node (ref "Q13") (pin "1") (pinfunction "G_1") (pintype "passive"))
      (node (ref "R15") (pin "2") (pinfunction "2_2") (pintype "passive"))
    )
    (net (code "105") (name "Net-(Q14-G)") (class "Default")
      (node (ref "Q14") (pin "1") (pinfunction "G_1") (pintype "passive"))
      (node (ref "R16") (pin "2") (pinfunction "2_2") (pintype "passive"))
    )
    (net (code "106") (name "Net-(Q15-G)") (class "Default")
      (node (ref "Q15") (pin "1") (pinfunction "G_1") (pintype "passive"))
      (node (ref "R17") (pin "2") (pinfunction "2_2") (pintype "passive"))
    )
    (net (code "107") (name "Net-(Q16-G)") (class "Default")
      (node (ref "Q16") (pin "1") (pinfunction "G_1") (pintype "passive"))
      (node (ref "R18") (pin "2") (pinfunction "2_2") (pintype "passive"))
    )
    (net (code "108") (name "Net-(RN1B-1)") (class "Default")
      (node (ref "JP14") (pin "2") (pinfunction "2_2") (pintype "passive"))
      (node (ref "JP2") (pin "2") (pinfunction "2_2") (pintype "passive"))
      (node (ref "R34") (pin "2") (pinfunction "2_2") (pintype "passive"))
      (node (ref "R46") (pin "1") (pinfunction "1_1") (pintype "passive"))
      (node (ref "RN1") (pin "2") (pinfunction "1_2") (pintype "passive"))
      (node (ref "RN2") (pin "8") (pinfunction "8_8") (pintype "passive"))
    )
    (net (code "109") (name "Net-(RN1C-1)") (class "Default")
      (node (ref "JP14") (pin "3") (pinfunction "3_3") (pintype "passive"))
      (node (ref "JP2") (pin "3") (pinfunction "3_3") (pintype "passive"))
      (node (ref "R33") (pin "2") (pinfunction "2_2") (pintype "passive"))
      (node (ref "R47") (pin "1") (pinfunction "1_1") (pintype "passive"))
      (node (ref "RN1") (pin "3") (pinfunction "1_3") (pintype "passive"))
      (node (ref "RN2") (pin "7") (pinfunction "7_7") (pintype "passive"))
    )
    (net (code "110") (name "Net-(RN1D-1)") (class "Default")
      (node (ref "JP14") (pin "4") (pinfunction "4_4") (pintype "passive"))
      (node (ref "JP2") (pin "4") (pinfunction "4_4") (pintype "passive"))
      (node (ref "R32") (pin "2") (pinfunction "2_2") (pintype "passive"))
      (node (ref "R48") (pin "1") (pinfunction "1_1") (pintype "passive"))
      (node (ref "RN1") (pin "4") (pinfunction "1_4") (pintype "passive"))
      (node (ref "RN2") (pin "6") (pinfunction "6_6") (pintype "passive"))
    )
    (net (code "111") (name "Net-(RN1E-1)") (class "Default")
      (node (ref "JP14") (pin "7") (pinfunction "7_7") (pintype "passive"))
      (node (ref "JP2") (pin "5") (pinfunction "5_5") (pintype "passive"))
      (node (ref "R31") (pin "2") (pinfunction "2_2") (pintype "passive"))
      (node (ref "R49") (pin "1") (pinfunction "1_1") (pintype "passive"))
      (node (ref "RN1") (pin "5") (pinfunction "1_5") (pintype "passive"))
      (node (ref "RN2") (pin "5") (pinfunction "5_5") (pintype "passive"))
    )
    (net (code "112") (name "Net-(RN1F-1)") (class "Default")
      (node (ref "JP14") (pin "8") (pinfunction "8_8") (pintype "passive"))
      (node (ref "JP2") (pin "6") (pinfunction "6_6") (pintype "passive"))
      (node (ref "R30") (pin "2") (pinfunction "2_2") (pintype "passive"))
      (node (ref "R50") (pin "1") (pinfunction "1_1") (pintype "passive"))
      (node (ref "RN1") (pin "6") (pinfunction "1_6") (pintype "passive"))
      (node (ref "RN2") (pin "4") (pinfunction "4_4") (pintype "passive"))
    )
    (net (code "113") (name "Net-(RN1G-1)") (class "Default")
      (node (ref "JP14") (pin "9") (pinfunction "9_9") (pintype "passive"))
      (node (ref "JP2") (pin "7") (pinfunction "7_7") (pintype "passive"))
      (node (ref "R29") (pin "2") (pinfunction "2_2") (pintype "passive"))
      (node (ref "R51") (pin "1") (pinfunction "1_1") (pintype "passive"))
      (node (ref "RN1") (pin "7") (pinfunction "1_7") (pintype "passive"))
      (node (ref "RN2") (pin "3") (pinfunction "3_3") (pintype "passive"))
    )
    (net (code "114") (name "Net-(RN1H-1)") (class "Default")
      (node (ref "JP14") (pin "10") (pinfunction "10_10") (pintype "passive"))
      (node (ref "JP2") (pin "8") (pinfunction "8_8") (pintype "passive"))
      (node (ref "R28") (pin "2") (pinfunction "2_2") (pintype "passive"))
      (node (ref "R52") (pin "1") (pinfunction "1_1") (pintype "passive"))
      (node (ref "RN1") (pin "8") (pinfunction "1_8") (pintype "passive"))
      (node (ref "RN2") (pin "2") (pinfunction "2_2") (pintype "passive"))
    )
    (net (code "115") (name "Net-(RN3B-1)") (class "Default")
      (node (ref "JP13") (pin "2") (pinfunction "2_2") (pintype "passive"))
      (node (ref "JP3") (pin "2") (pinfunction "2_2") (pintype "passive"))
      (node (ref "R43") (pin "2") (pinfunction "2_2") (pintype "passive"))
      (node (ref "R54") (pin "2") (pinfunction "2_2") (pintype "passive"))
      (node (ref "RN3") (pin "2") (pinfunction "1_2") (pintype "passive"))
      (node (ref "RN4") (pin "8") (pinfunction "8_8") (pintype "passive"))
    )
    (net (code "116") (name "Net-(RN3C-1)") (class "Default")
      (node (ref "JP13") (pin "3") (pinfunction "3_3") (pintype "passive"))
      (node (ref "JP3") (pin "3") (pinfunction "3_3") (pintype "passive"))
      (node (ref "R42") (pin "2") (pinfunction "2_2") (pintype "passive"))
      (node (ref "R55") (pin "2") (pinfunction "2_2") (pintype "passive"))
      (node (ref "RN3") (pin "3") (pinfunction "1_3") (pintype "passive"))
      (node (ref "RN4") (pin "7") (pinfunction "7_7") (pintype "passive"))
    )
    (net (code "117") (name "Net-(RN3D-1)") (class "Default")
      (node (ref "JP13") (pin "4") (pinfunction "4_4") (pintype "passive"))
      (node (ref "JP3") (pin "4") (pinfunction "4_4") (pintype "passive"))
      (node (ref "R41") (pin "2") (pinfunction "2_2") (pintype "passive"))
      (node (ref "R56") (pin "2") (pinfunction "2_2") (pintype "passive"))
      (node (ref "RN3") (pin "4") (pinfunction "1_4") (pintype "passive"))
      (node (ref "RN4") (pin "6") (pinfunction "6_6") (pintype "passive"))
    )
    (net (code "118") (name "Net-(RN3E-1)") (class "Default")
      (node (ref "JP13") (pin "7") (pinfunction "7_7") (pintype "passive"))
      (node (ref "JP3") (pin "5") (pinfunction "5_5") (pintype "passive"))
      (node (ref "R39") (pin "2") (pinfunction "2_2") (pintype "passive"))
      (node (ref "R57") (pin "2") (pinfunction "2_2") (pintype "passive"))
      (node (ref "RN3") (pin "5") (pinfunction "1_5") (pintype "passive"))
      (node (ref "RN4") (pin "5") (pinfunction "5_5") (pintype "passive"))
    )
    (net (code "119") (name "Net-(RN3F-1)") (class "Default")
      (node (ref "JP13") (pin "8") (pinfunction "8_8") (pintype "passive"))
      (node (ref "JP3") (pin "6") (pinfunction "6_6") (pintype "passive"))
      (node (ref "R38") (pin "2") (pinfunction "2_2") (pintype "passive"))
      (node (ref "R58") (pin "2") (pinfunction "2_2") (pintype "passive"))
      (node (ref "RN3") (pin "6") (pinfunction "1_6") (pintype "passive"))
      (node (ref "RN4") (pin "4") (pinfunction "4_4") (pintype "passive"))
    )
    (net (code "120") (name "Net-(RN3G-1)") (class "Default")
      (node (ref "JP13") (pin "9") (pinfunction "9_9") (pintype "passive"))
      (node (ref "JP3") (pin "7") (pinfunction "7_7") (pintype "passive"))
      (node (ref "R37") (pin "2") (pinfunction "2_2") (pintype "passive"))
      (node (ref "R59") (pin "2") (pinfunction "2_2") (pintype "passive"))
      (node (ref "RN3") (pin "7") (pinfunction "1_7") (pintype "passive"))
      (node (ref "RN4") (pin "3") (pinfunction "3_3") (pintype "passive"))
    )
    (net (code "121") (name "Net-(RN3H-1)") (class "Default")
      (node (ref "JP13") (pin "10") (pinfunction "10_10") (pintype "passive"))
      (node (ref "JP3") (pin "8") (pinfunction "8_8") (pintype "passive"))
      (node (ref "R36") (pin "2") (pinfunction "2_2") (pintype "passive"))
      (node (ref "R60") (pin "2") (pinfunction "2_2") (pintype "passive"))
      (node (ref "RN3") (pin "8") (pinfunction "1_8") (pintype "passive"))
      (node (ref "RN4") (pin "2") (pinfunction "2_2") (pintype "passive"))
    )
    (net (code "122") (name "Net-(SJ13-1)") (class "Default")
      (node (ref "SJ13") (pin "P$1") (pinfunction "1_P$1") (pintype "passive"))
      (node (ref "U$1") (pin "PB14") (pinfunction "PB14_PB14") (pintype "bidirectional"))
    )
    (net (code "123") (name "Net-(SJ14-1)") (class "Default")
      (node (ref "SJ14") (pin "P$1") (pinfunction "1_P$1") (pintype "passive"))
      (node (ref "U$1") (pin "VIN2") (pinfunction "VIN2_VIN2") (pintype "power_in"))
    )
    (net (code "124") (name "Net-(SJ16-2)") (class "Default")
      (node (ref "JP9") (pin "2") (pinfunction "2_2") (pintype "passive"))
      (node (ref "SJ15") (pin "2") (pinfunction "2_2") (pintype "passive"))
      (node (ref "SJ16") (pin "P$2") (pinfunction "2_P$2") (pintype "passive"))
    )
    (net (code "125") (name "Net-(SJ18-2)") (class "Default")
      (node (ref "SJ18") (pin "P$2") (pinfunction "2_P$2") (pintype "passive"))
      (node (ref "U7") (pin "5") (pinfunction "VREF_5") (pintype "output"))
      (node (ref "U7B") (pin "5") (pinfunction "VREF_5") (pintype "bidirectional"))
    )
    (net (code "126") (name "Net-(U7-RS)") (class "Default")
      (node (ref "R61") (pin "1") (pinfunction "1_1") (pintype "passive"))
      (node (ref "U7") (pin "8") (pinfunction "RS_8") (pintype "input"))
      (node (ref "U7B") (pin "8") (pinfunction "RS_8") (pintype "bidirectional"))
    )
    (net (code "127") (name "Net-(U8-VOUT)") (class "Default")
      (node (ref "D1") (pin "C") (pinfunction "C_C") (pintype "passive"))
      (node (ref "L1") (pin "2") (pinfunction "2_2") (pintype "passive"))
      (node (ref "U8") (pin "2") (pinfunction "VOUT_2") (pintype "bidirectional"))
      (node (ref "U8B") (pin "7") (pinfunction "OUT_7") (pintype "passive"))
    )
    (net (code "128") (name "OLAT") (class "Default")
      (node (ref "IC3") (pin "12") (pinfunction "RCK_12") (pintype "input"))
      (node (ref "IC5") (pin "12") (pinfunction "RCK_12") (pintype "input"))
      (node (ref "R21") (pin "1") (pinfunction "1_1") (pintype "passive"))
      (node (ref "U$1") (pin "PA8") (pinfunction "PA8_PA8") (pintype "bidirectional"))
    )
    (net (code "129") (name "SCK") (class "Default")
      (node (ref "IC3") (pin "11") (pinfunction "SCK_11") (pintype "input"))
      (node (ref "IC5") (pin "11") (pinfunction "SCK_11") (pintype "input"))
      (node (ref "JP9") (pin "3") (pinfunction "3_3") (pintype "passive"))
      (node (ref "R19") (pin "1") (pinfunction "1_1") (pintype "passive"))
      (node (ref "U$1") (pin "PB3") (pinfunction "PB3_PB3") (pintype "bidirectional"))
    )
    (net (code "130") (name "SCK2") (class "Default")
      (node (ref "IC1") (pin "7") (pinfunction "CLK_7") (pintype "input"))
      (node (ref "IC4") (pin "7") (pinfunction "CLK_7") (pintype "input"))
      (node (ref "U$1") (pin "PB10") (pinfunction "PB10_PB10") (pintype "bidirectional"))
    )
    (net (code "131") (name "SLNK1") (class "Default")
      (node (ref "IC3") (pin "14") (pinfunction "SER_14") (pintype "input"))
      (node (ref "IC5") (pin "9") (pinfunction "QH*_9") (pintype "tri_state"))
      (node (ref "SJ17") (pin "P$1") (pinfunction "1_P$1") (pintype "passive"))
    )
    (net (code "132") (name "SLNK2") (class "Default")
      (node (ref "IC3") (pin "9") (pinfunction "QH*_9") (pintype "tri_state"))
      (node (ref "SJ16") (pin "P$1") (pinfunction "1_P$1") (pintype "passive"))
    )
    (net (code "133") (name "SLNK3") (class "Default")
      (node (ref "IC1") (pin "13") (pinfunction "QH_13") (pintype "output"))
      (node (ref "IC4") (pin "1") (pinfunction "SER_1") (pintype "input"))
    )
    (net (code "134") (name "SRV1") (class "Default")
      (node (ref "JP7") (pin "2") (pinfunction "2_2") (pintype "passive"))
      (node (ref "R25") (pin "2") (pinfunction "2_2") (pintype "passive"))
      (node (ref "U$1") (pin "PC9") (pinfunction "PC9_PC9") (pintype "bidirectional"))
    )
    (net (code "135") (name "SRV2") (class "Default")
      (node (ref "JP7") (pin "1") (pinfunction "1_1") (pintype "passive"))
      (node (ref "R24") (pin "2") (pinfunction "2_2") (pintype "passive"))
      (node (ref "U$1") (pin "PC7") (pinfunction "PC7_PC7") (pintype "bidirectional"))
    )
    (net (code "136") (name "SRV3") (class "Default")
      (node (ref "JP11") (pin "2") (pinfunction "2_2") (pintype "passive"))
      (node (ref "R26") (pin "2") (pinfunction "2_2") (pintype "passive"))
      (node (ref "U$1") (pin "PC8") (pinfunction "PC8_PC8") (pintype "bidirectional"))
    )
    (net (code "137") (name "SRV4") (class "Default")
      (node (ref "JP11") (pin "1") (pinfunction "1_1") (pintype "passive"))
      (node (ref "R27") (pin "2") (pinfunction "2_2") (pintype "passive"))
      (node (ref "U$1") (pin "PC6") (pinfunction "PC6_PC6") (pintype "bidirectional"))
    )
    (net (code "138") (name "SRV5") (class "Default")
      (node (ref "JP12") (pin "2") (pinfunction "2_2") (pintype "passive"))
      (node (ref "R64") (pin "2") (pinfunction "2_2") (pintype "passive"))
      (node (ref "U$1") (pin "PF1-PH1") (pinfunction "PF1-PH1_PF1-PH1") (pintype "bidirectional"))
    )
    (net (code "139") (name "SRV6") (class "Default")
      (node (ref "JP12") (pin "1") (pinfunction "1_1") (pintype "passive"))
      (node (ref "R65") (pin "2") (pinfunction "2_2") (pintype "passive"))
      (node (ref "U$1") (pin "PA15") (pinfunction "PA15_PA15") (pintype "bidirectional"))
    )
    (net (code "140") (name "SRV7") (class "Default")
      (node (ref "JP16") (pin "2") (pinfunction "2_2") (pintype "passive"))
      (node (ref "R66") (pin "2") (pinfunction "2_2") (pintype "passive"))
      (node (ref "U$1") (pin "PC12") (pinfunction "PC12_PC12") (pintype "bidirectional"))
    )
    (net (code "141") (name "SRV8") (class "Default")
      (node (ref "JP16") (pin "1") (pinfunction "1_1") (pintype "passive"))
      (node (ref "R67") (pin "2") (pinfunction "2_2") (pintype "passive"))
      (node (ref "U$1") (pin "PD2") (pinfunction "PD2_PD2") (pintype "bidirectional"))
    )
    (net (code "142") (name "TIN1") (class "Default")
      (node (ref "IC9") (pin "3") (pinfunction "+IN_3") (pintype "input"))
      (node (ref "U$1") (pin "PB2") (pinfunction "PB2_PB2") (pintype "bidirectional"))
      (node (ref "U$3") (pin "4") (pinfunction "I_4") (pintype "input"))
    )
    (net (code "143") (name "TIN2") (class "Default")
      (node (ref "IC9") (pin "5") (pinfunction "+IN_5") (pintype "input"))
      (node (ref "U$1") (pin "PB1") (pinfunction "PB1_PB1") (pintype "bidirectional"))
      (node (ref "U$2") (pin "2") (pinfunction "I_2") (pintype "input"))
    )
    (net (code "144") (name "TIN3") (class "Default")
      (node (ref "IC9") (pin "10") (pinfunction "+IN_10") (pintype "input"))
      (node (ref "U$1") (pin "PB15") (pinfunction "PB15_PB15") (pintype "bidirectional"))
      (node (ref "U$2") (pin "4") (pinfunction "I_4") (pintype "input"))
    )
    (net (code "145") (name "TIN4") (class "Default")
      (node (ref "IC9") (pin "12") (pinfunction "+IN_12") (pintype "input"))
      (node (ref "U$1") (pin "PB12") (pinfunction "PB12_PB12") (pintype "bidirectional"))
      (node (ref "U$3") (pin "2") (pinfunction "I_2") (pintype "input"))
    )
    (net (code "146") (name "TIN5") (class "Default")
      (node (ref "IC6") (pin "3") (pinfunction "+IN_3") (pintype "input"))
      (node (ref "U$1") (pin "PA4") (pinfunction "PA4_PA4") (pintype "bidirectional"))
      (node (ref "U$5") (pin "4") (pinfunction "I_4") (pintype "input"))
    )
    (net (code "147") (name "TIN6") (class "Default")
      (node (ref "IC6") (pin "5") (pinfunction "+IN_5") (pintype "input"))
      (node (ref "U$1") (pin "PC0") (pinfunction "PC0_PC0") (pintype "bidirectional"))
      (node (ref "U$4") (pin "2") (pinfunction "I_2") (pintype "input"))
    )
    (net (code "148") (name "TIN7") (class "Default")
      (node (ref "IC6") (pin "10") (pinfunction "+IN_10") (pintype "input"))
      (node (ref "U$1") (pin "PC3") (pinfunction "PC3_PC3") (pintype "bidirectional"))
      (node (ref "U$4") (pin "4") (pinfunction "I_4") (pintype "input"))
    )
    (net (code "149") (name "TIN8") (class "Default")
      (node (ref "IC6") (pin "12") (pinfunction "+IN_12") (pintype "input"))
      (node (ref "U$1") (pin "PA0") (pinfunction "PA0_PA0") (pintype "bidirectional"))
      (node (ref "U$5") (pin "2") (pinfunction "I_2") (pintype "input"))
    )
    (net (code "150") (name "V+") (class "Default")
      (node (ref "C1") (pin "1") (pinfunction "1_1") (pintype "passive"))
      (node (ref "C2") (pin "+") (pinfunction "+_+") (pintype "passive"))
      (node (ref "L1") (pin "1") (pinfunction "1_1") (pintype "passive"))
      (node (ref "U$1") (pin "E5V") (pinfunction "E5V_E5V") (pintype "power_in"))
      (node (ref "U8") (pin "3") (pinfunction "FB_3") (pintype "bidirectional"))
      (node (ref "U8B") (pin "1") (pinfunction "FB_1") (pintype "input"))
    )
    (net (code "151") (name "unconnected-(H1-MOUNT-PadB3,3)") (class "Default")
      (node (ref "H1") (pin "B3,3") (pinfunction "MOUNT_B3,3") (pintype "passive"))
    )
    (net (code "152") (name "unconnected-(H2-MOUNT-PadB3,3)") (class "Default")
      (node (ref "H2") (pin "B3,3") (pinfunction "MOUNT_B3,3") (pintype "passive"))
    )
    (net (code "153") (name "unconnected-(H3-MOUNT-PadB3,3)") (class "Default")
      (node (ref "H3") (pin "B3,3") (pinfunction "MOUNT_B3,3") (pintype "passive"))
    )
    (net (code "154") (name "unconnected-(H4-MOUNT-PadB3,3)") (class "Default")
      (node (ref "H4") (pin "B3,3") (pinfunction "MOUNT_B3,3") (pintype "passive"))
    )
    (net (code "155") (name "unconnected-(U$1-PadBOOT0)") (class "Default")
      (node (ref "U$1") (pin "BOOT0") (pinfunction "BOOT0_BOOT0") (pintype "bidirectional"))
    )
    (net (code "156") (name "unconnected-(U$1-PadIOREF2)") (class "Default")
      (node (ref "U$1") (pin "IOREF2") (pinfunction "IOREF2_IOREF2") (pintype "input"))
    )
    (net (code "157") (name "unconnected-(U$1-PadNC1-PF7)") (class "Default")
      (node (ref "U$1") (pin "NC1-PF7") (pinfunction "NC1-PF7_NC1-PF7") (pintype "bidirectional"))
    )
    (net (code "158") (name "unconnected-(U$1-PadNC2-PF6)") (class "Default")
      (node (ref "U$1") (pin "NC2-PF6") (pinfunction "NC2-PF6_NC2-PF6") (pintype "bidirectional"))
    )
    (net (code "159") (name "unconnected-(U$1-PadNC3)") (class "Default")
      (node (ref "U$1") (pin "NC3") (pinfunction "NC3_NC3") (pintype "no_connect"))
    )
    (net (code "160") (name "unconnected-(U$1-PadNC4)") (class "Default")
      (node (ref "U$1") (pin "NC4") (pinfunction "NC4_NC4") (pintype "no_connect"))
    )
    (net (code "161") (name "unconnected-(U$1-PadNC5-PD8)") (class "Default")
      (node (ref "U$1") (pin "NC5-PD8") (pinfunction "NC5-PD8_NC5-PD8") (pintype "bidirectional"))
    )
    (net (code "162") (name "unconnected-(U$1-PadNC6-PB11)") (class "Default")
      (node (ref "U$1") (pin "NC6-PB11") (pinfunction "NC6-PB11_NC6-PB11") (pintype "no_connect"))
    )
    (net (code "163") (name "unconnected-(U$1-PadNC7-PF5)") (class "Default")
      (node (ref "U$1") (pin "NC7-PF5") (pinfunction "NC7-PF5_NC7-PF5") (pintype "bidirectional"))
    )
    (net (code "164") (name "unconnected-(U$1-PadNC8-PF4)") (class "Default")
      (node (ref "U$1") (pin "NC8-PF4") (pinfunction "NC8-PF4_NC8-PF4") (pintype "bidirectional"))
    )
    (net (code "165") (name "unconnected-(U$1-PadNRESET)") (class "Default")
      (node (ref "U$1") (pin "NRESET") (pinfunction "NRESET_NRESET") (pintype "input"))
    )
    (net (code "166") (name "unconnected-(U$1-PadPA1)") (class "Default")
      (node (ref "U$1") (pin "PA1") (pinfunction "PA1_PA1") (pintype "bidirectional"))
    )
    (net (code "167") (name "unconnected-(U$1-PadPA2)") (class "Default")
      (node (ref "U$1") (pin "PA2") (pinfunction "PA2_PA2") (pintype "bidirectional"))
    )
    (net (code "168") (name "unconnected-(U$1-PadPA3)") (class "Default")
      (node (ref "U$1") (pin "PA3") (pinfunction "PA3_PA3") (pintype "bidirectional"))
    )
    (net (code "169") (name "unconnected-(U$1-PadPA5)") (class "Default")
      (node (ref "U$1") (pin "PA5") (pinfunction "PA5_PA5") (pintype "bidirectional"))
    )
    (net (code "170") (name "unconnected-(U$1-PadPA7)") (class "Default")
      (node (ref "U$1") (pin "PA7") (pinfunction "PA7_PA7") (pintype "bidirectional"))
    )
    (net (code "171") (name "unconnected-(U$1-PadPA9)") (class "Default")
      (node (ref "U$1") (pin "PA9") (pinfunction "PA9_PA9") (pintype "bidirectional"))
    )
    (net (code "172") (name "unconnected-(U$1-PadPA10)") (class "Default")
      (node (ref "U$1") (pin "PA10") (pinfunction "PA10_PA10") (pintype "bidirectional"))
    )
    (net (code "173") (name "unconnected-(U$1-PadPA11)") (class "Default")
      (node (ref "U$1") (pin "PA11") (pinfunction "PA11_PA11") (pintype "bidirectional"))
    )
    (net (code "174") (name "unconnected-(U$1-PadPA12)") (class "Default")
      (node (ref "U$1") (pin "PA12") (pinfunction "PA12_PA12") (pintype "bidirectional"))
    )
    (net (code "175") (name "unconnected-(U$1-PadPA13)") (class "Default")
      (node (ref "U$1") (pin "PA13") (pinfunction "PA13_PA13") (pintype "bidirectional"))
    )
    (net (code "176") (name "unconnected-(U$1-PadPA14)") (class "Default")
      (node (ref "U$1") (pin "PA14") (pinfunction "PA14_PA14") (pintype "bidirectional"))
    )
    (net (code "177") (name "unconnected-(U$1-PadPB0)") (class "Default")
      (node (ref "U$1") (pin "PB0") (pinfunction "PB0_PB0") (pintype "bidirectional"))
    )
    (net (code "178") (name "unconnected-(U$1-PadPB13)") (class "Default")
      (node (ref "U$1") (pin "PB13") (pinfunction "PB13_PB13") (pintype "bidirectional"))
    )
    (net (code "179") (name "unconnected-(U$1-PadPC1)") (class "Default")
      (node (ref "U$1") (pin "PC1") (pinfunction "PC1_PC1") (pintype "bidirectional"))
    )
    (net (code "180") (name "unconnected-(U$1-PadPC4)") (class "Default")
      (node (ref "U$1") (pin "PC4") (pinfunction "PC4_PC4") (pintype "bidirectional"))
    )
    (net (code "181") (name "unconnected-(U$1-PadPC5)") (class "Default")
      (node (ref "U$1") (pin "PC5") (pinfunction "PC5_PC5") (pintype "bidirectional"))
    )
    (net (code "182") (name "unconnected-(U$1-PadPC13)") (class "Default")
      (node (ref "U$1") (pin "PC13") (pinfunction "PC13_PC13") (pintype "bidirectional"))
    )
    (net (code "183") (name "unconnected-(U$1-PadPC14)") (class "Default")
      (node (ref "U$1") (pin "PC14") (pinfunction "PC14_PC14") (pintype "bidirectional"))
    )
    (net (code "184") (name "unconnected-(U$1-PadPC15)") (class "Default")
      (node (ref "U$1") (pin "PC15") (pinfunction "PC15_PC15") (pintype "bidirectional"))
    )
    (net (code "185") (name "unconnected-(U$1-PadPF0-PH0)") (class "Default")
      (node (ref "U$1") (pin "PF0-PH0") (pinfunction "PF0-PH0_PF0-PH0") (pintype "bidirectional"))
    )
  )
)
